# RFWBBoard.net
KiCad netlist of a schematic drawn in EAGLE
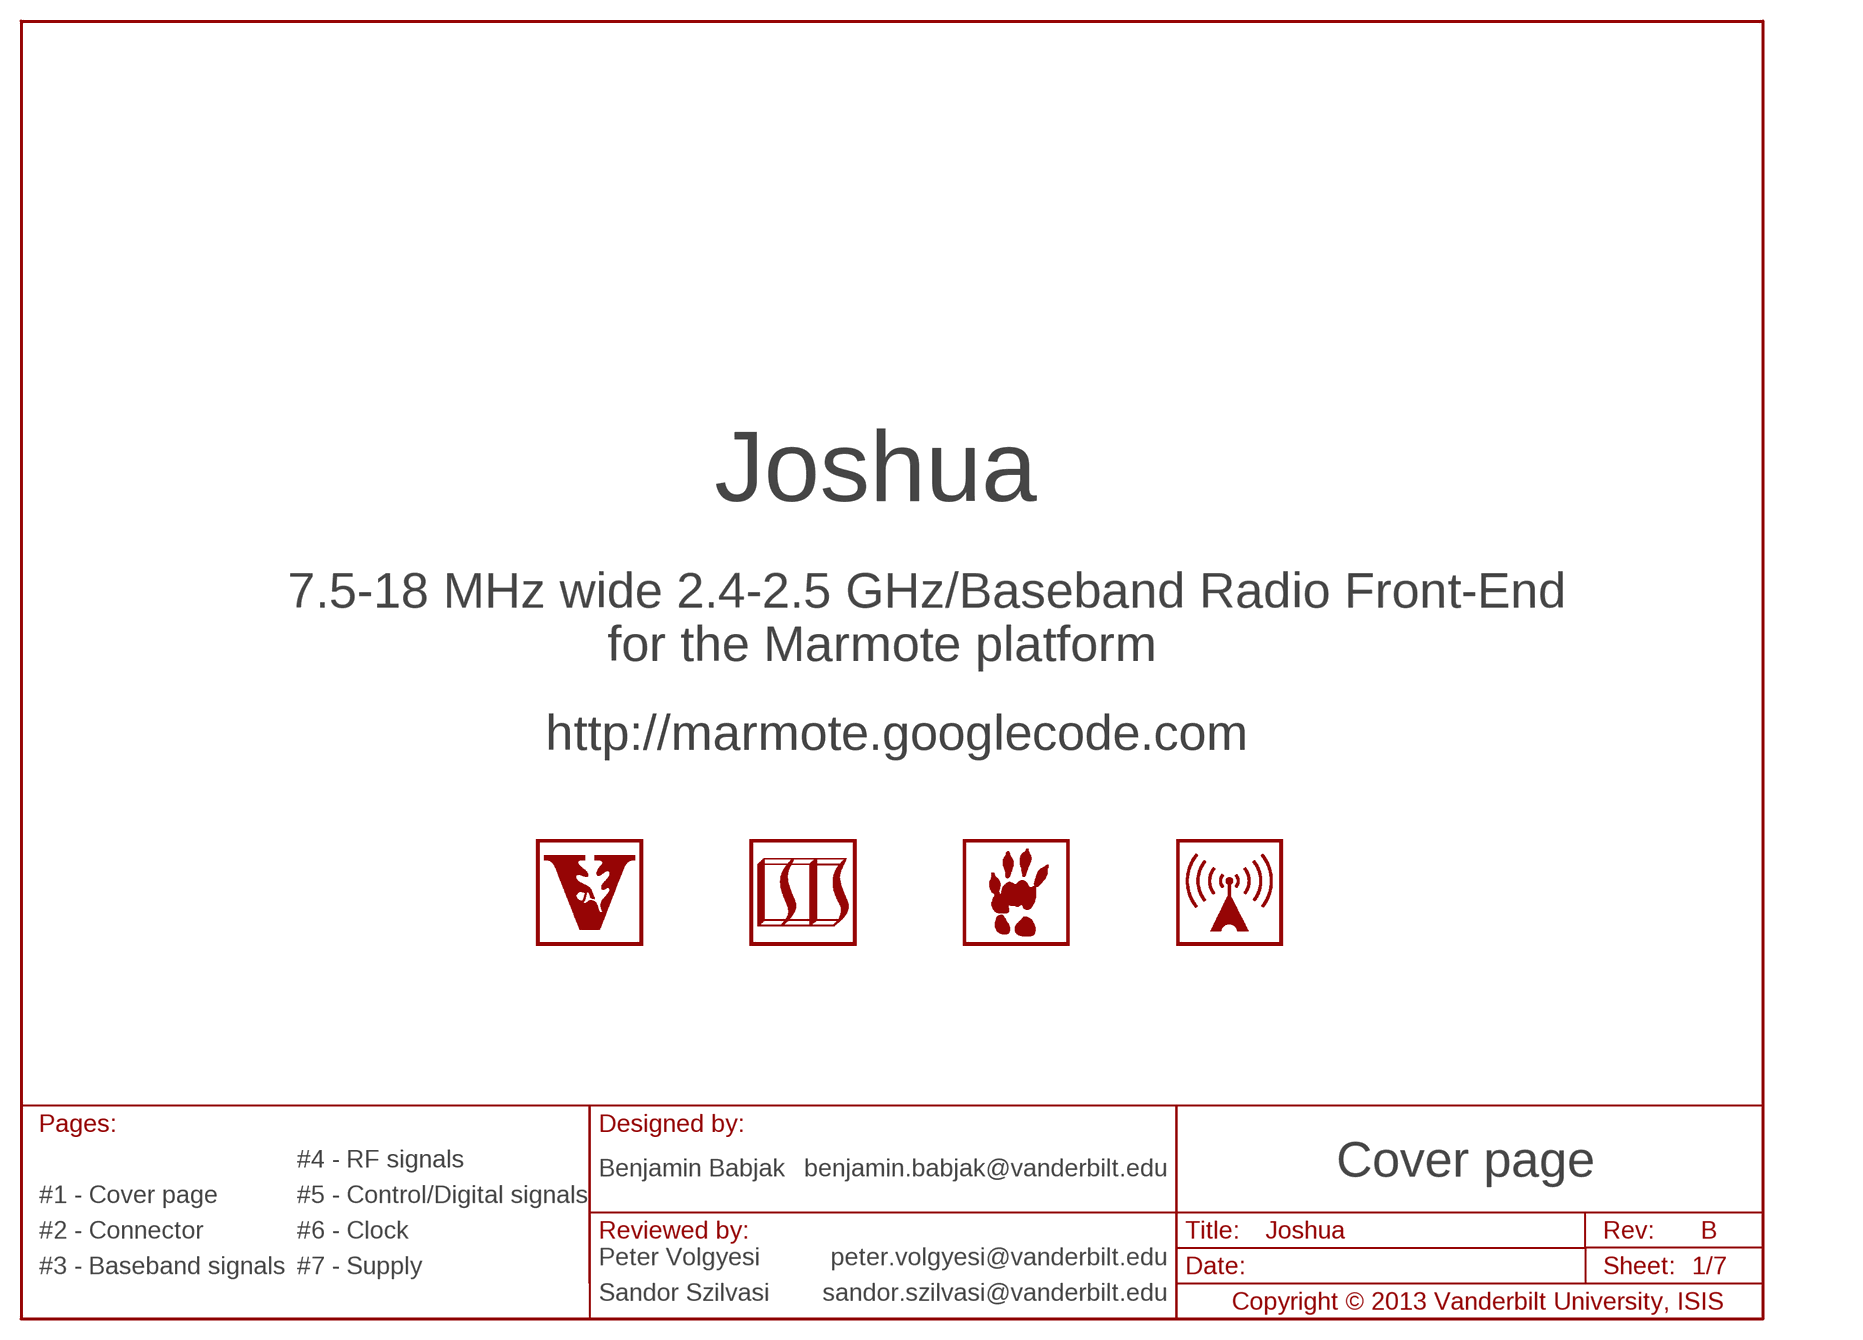
[diagram p0: schematic, sheet 1]
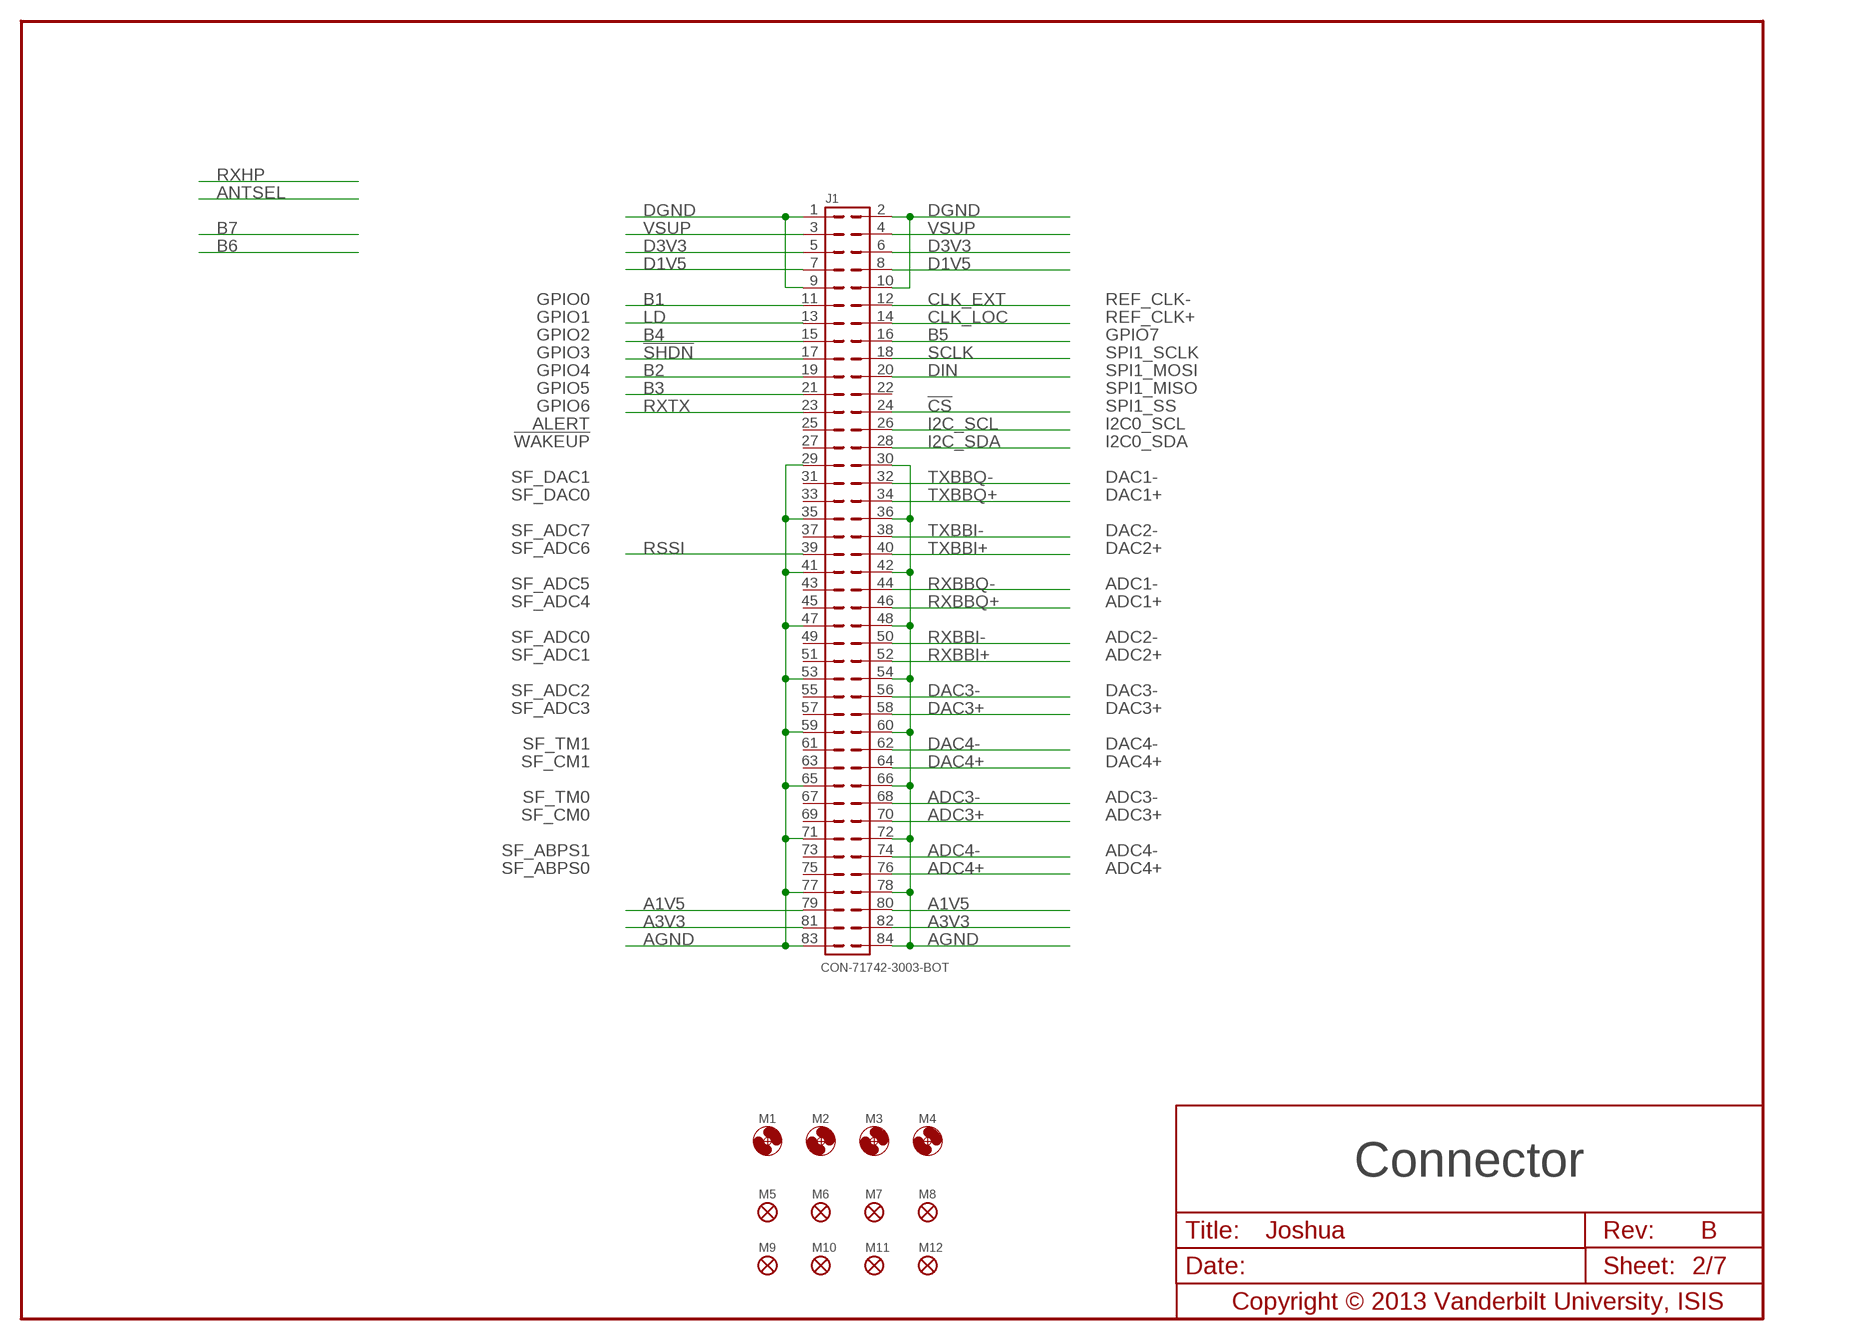
[diagram p1: schematic, sheet 2]
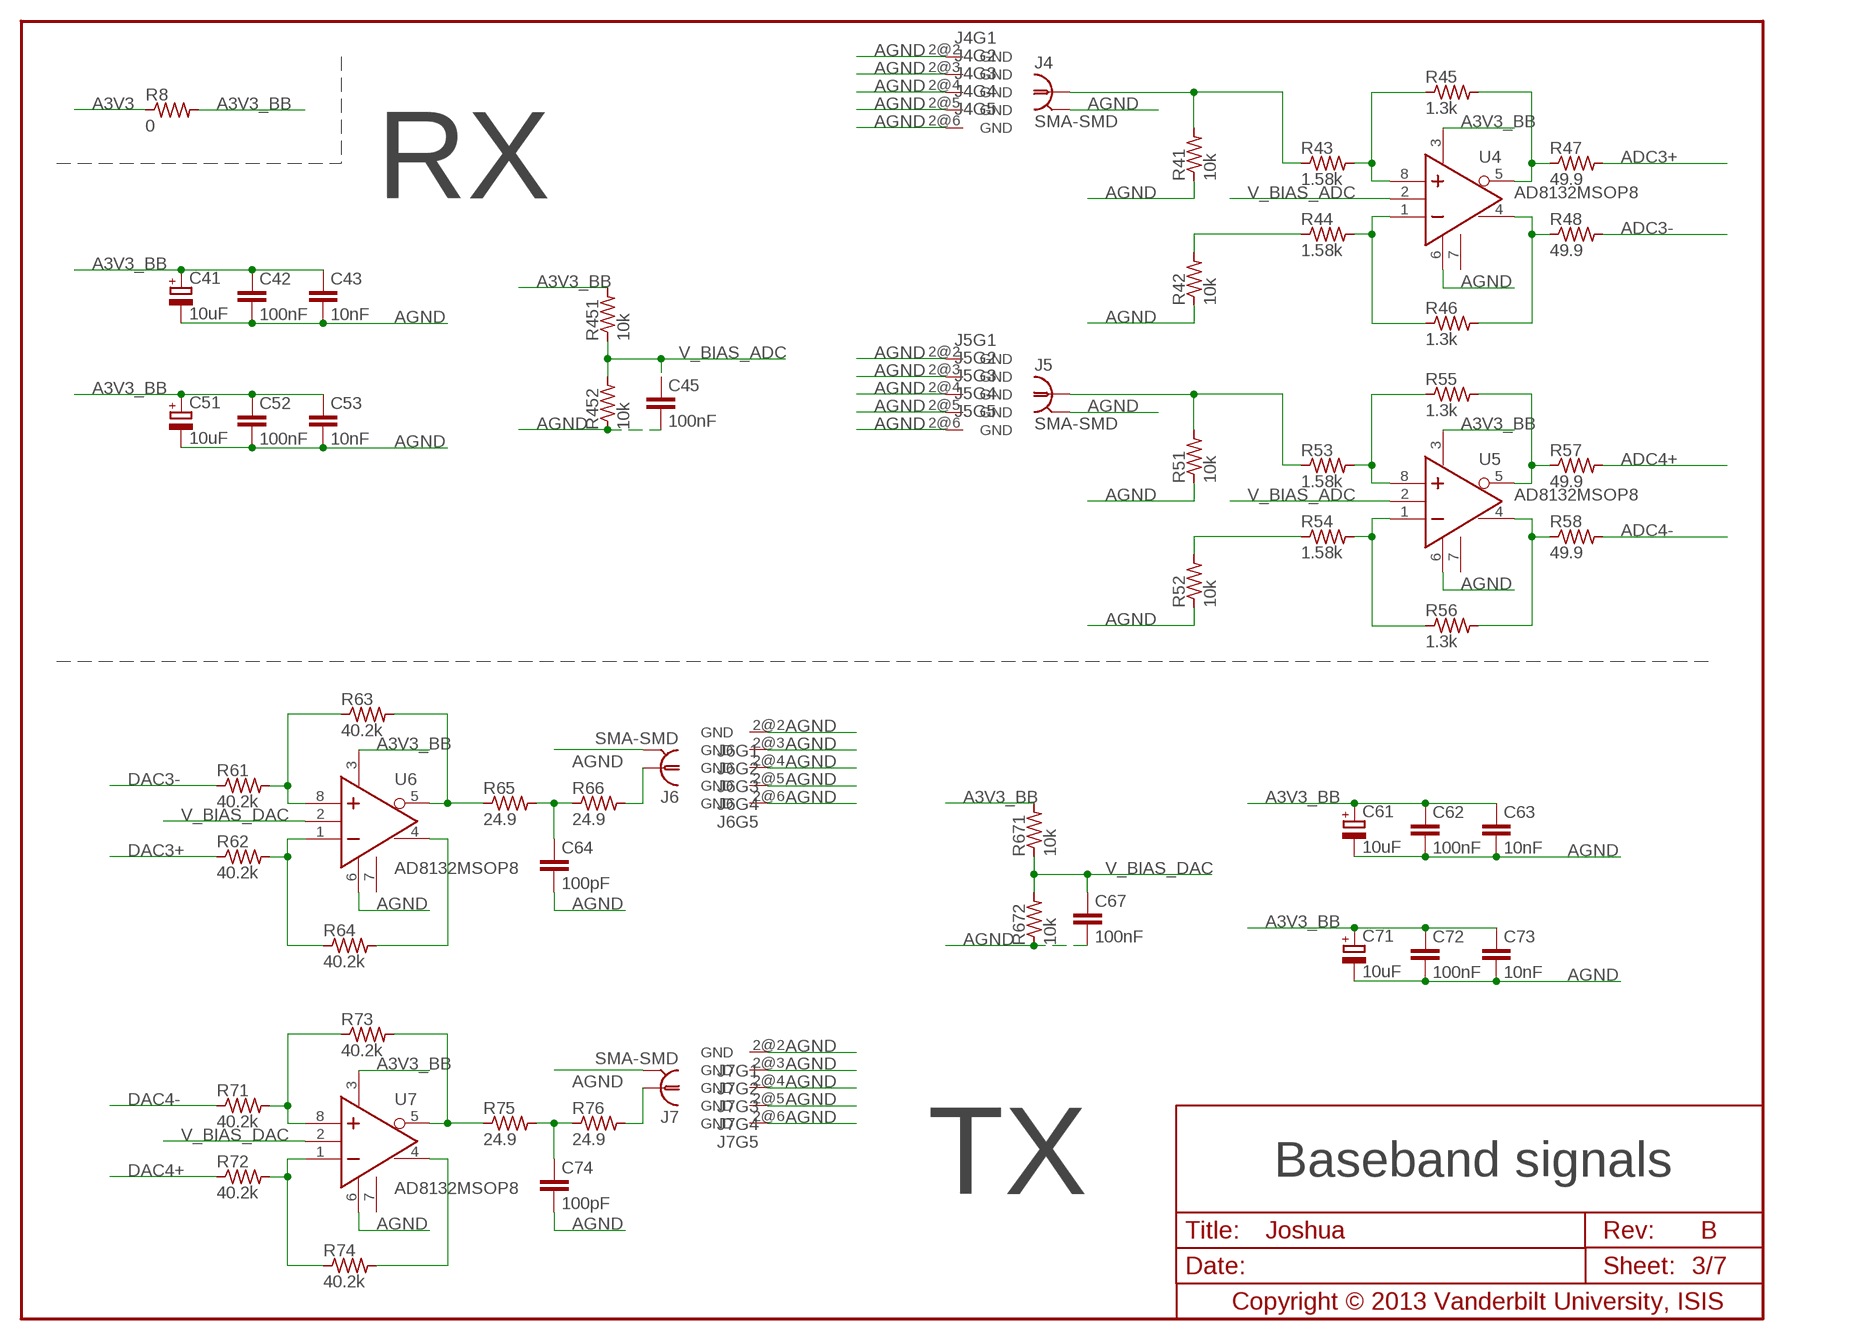
[diagram p2: schematic, sheet 3]
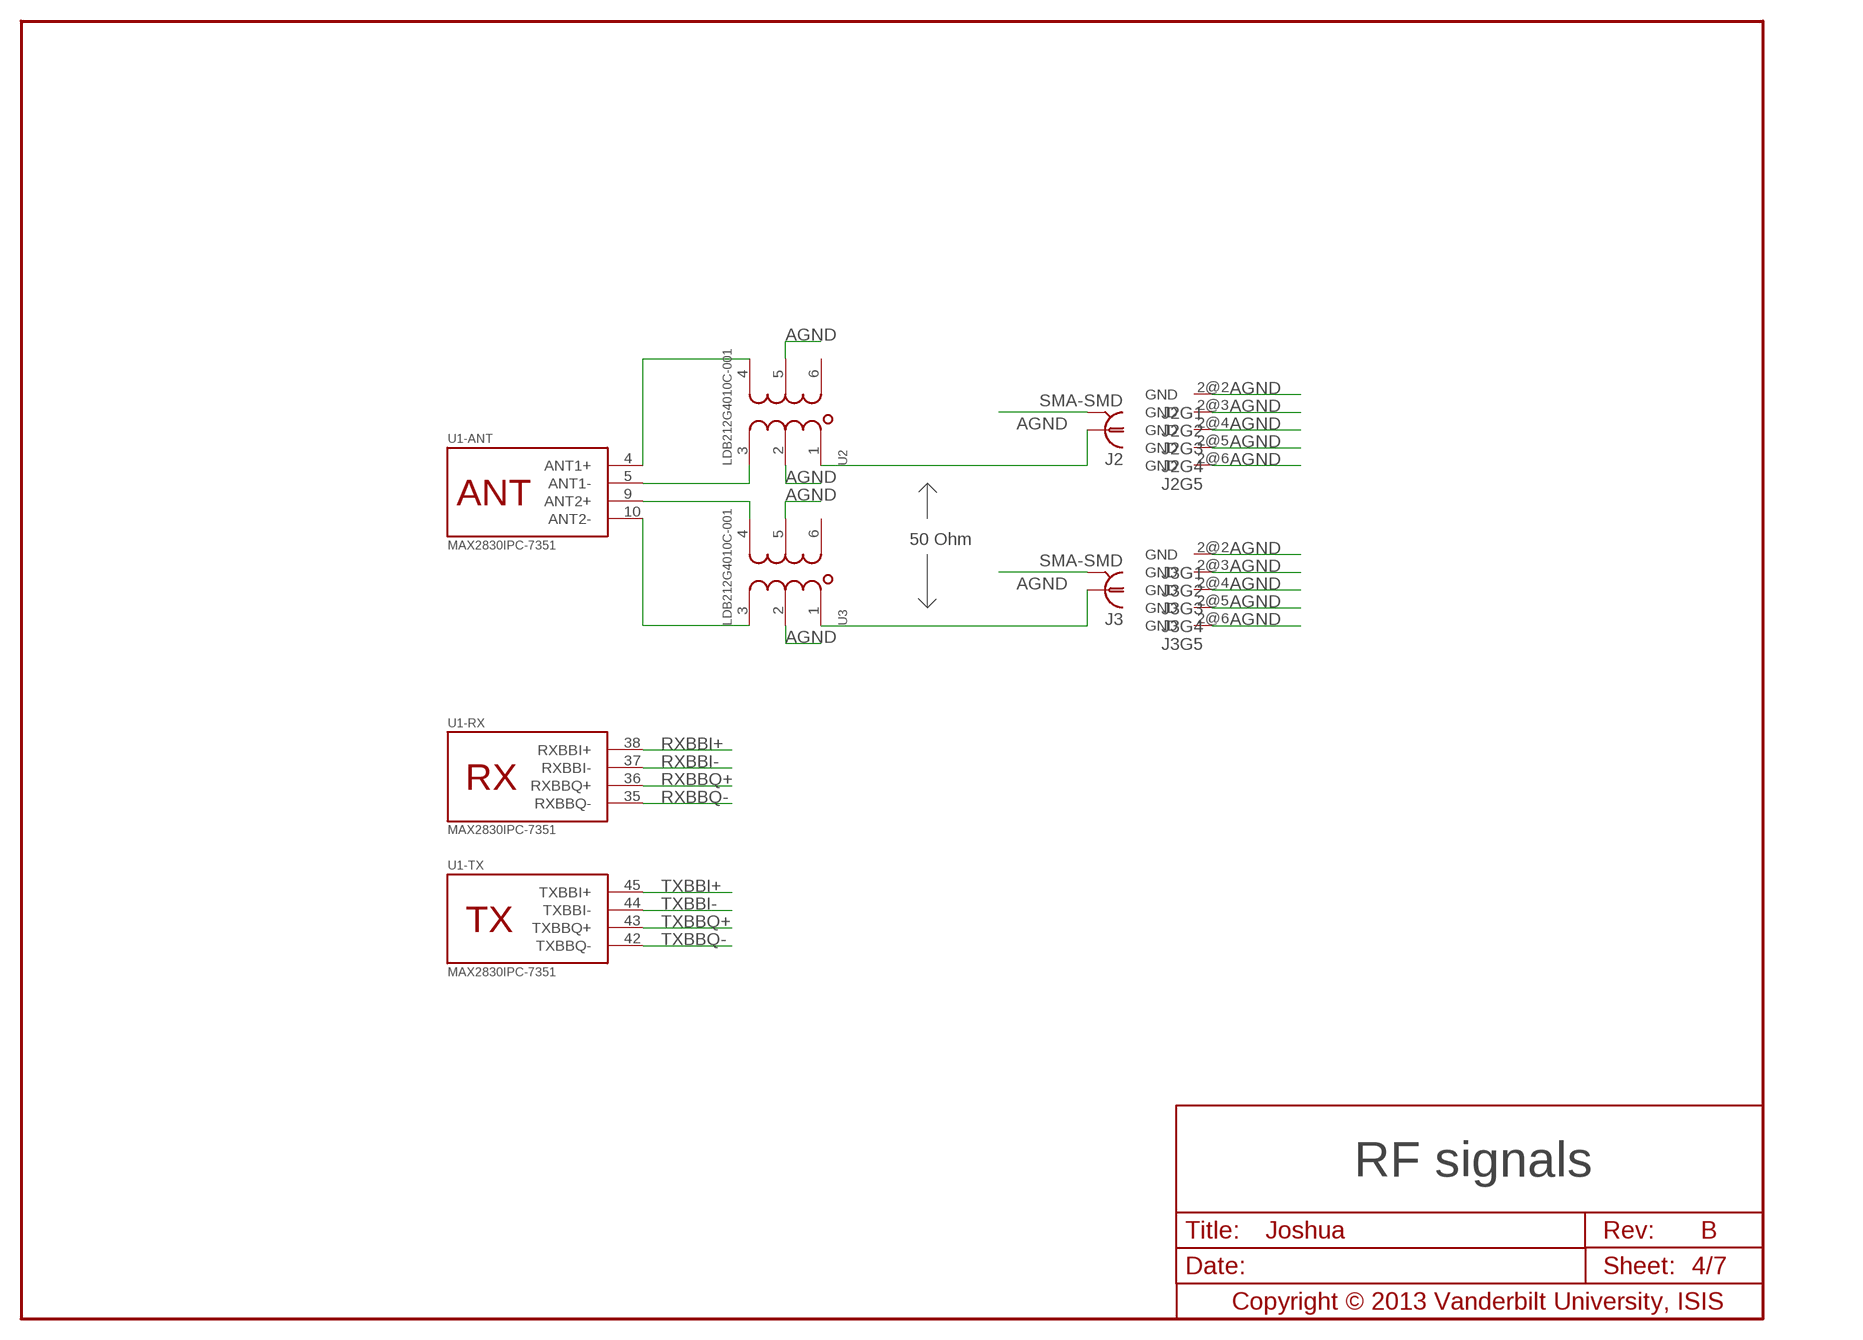
[diagram p3: schematic, sheet 4]
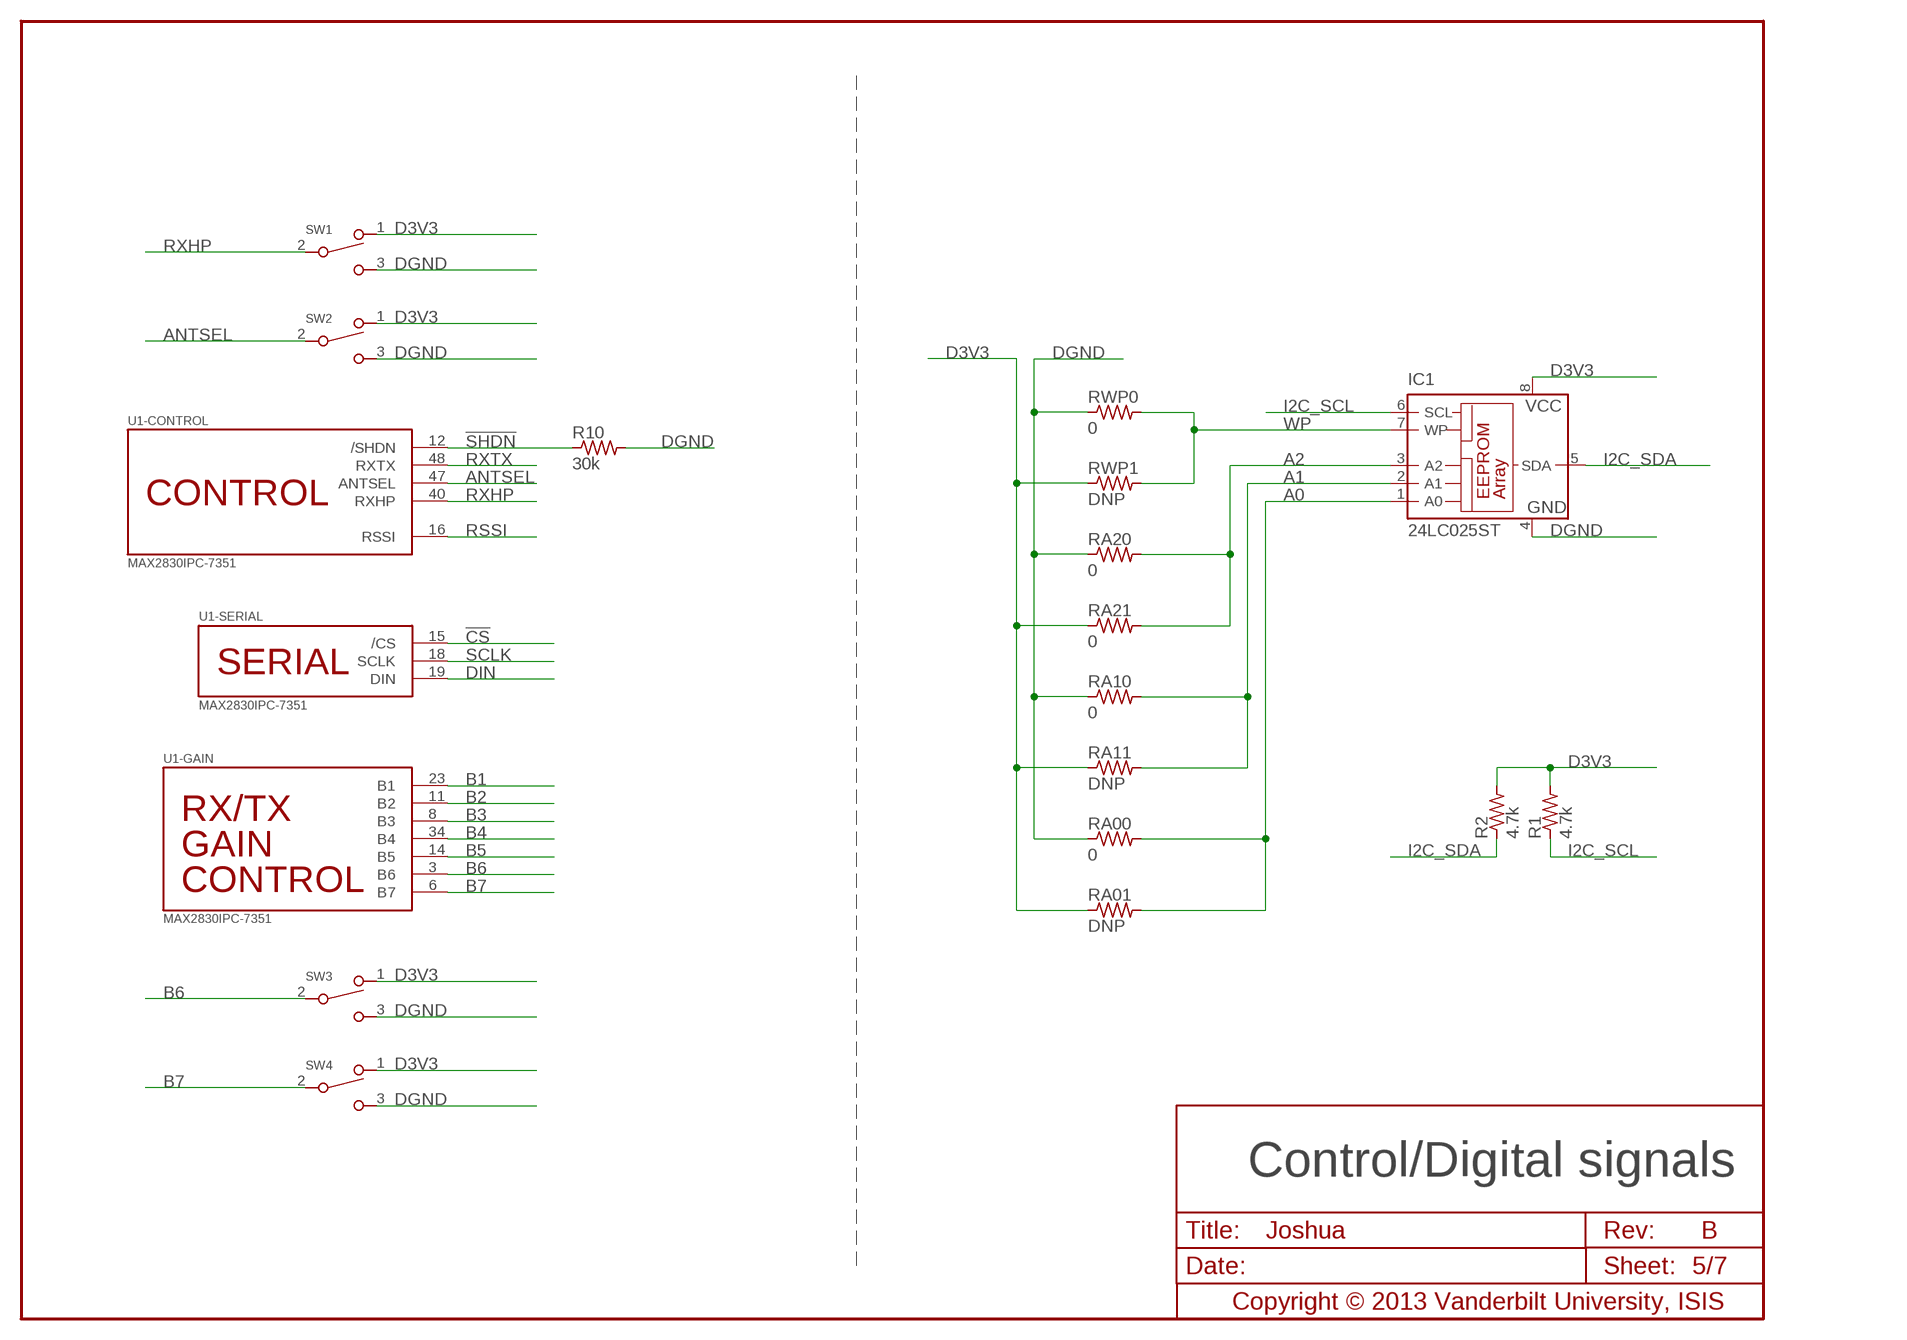
[diagram p4: schematic, sheet 5]
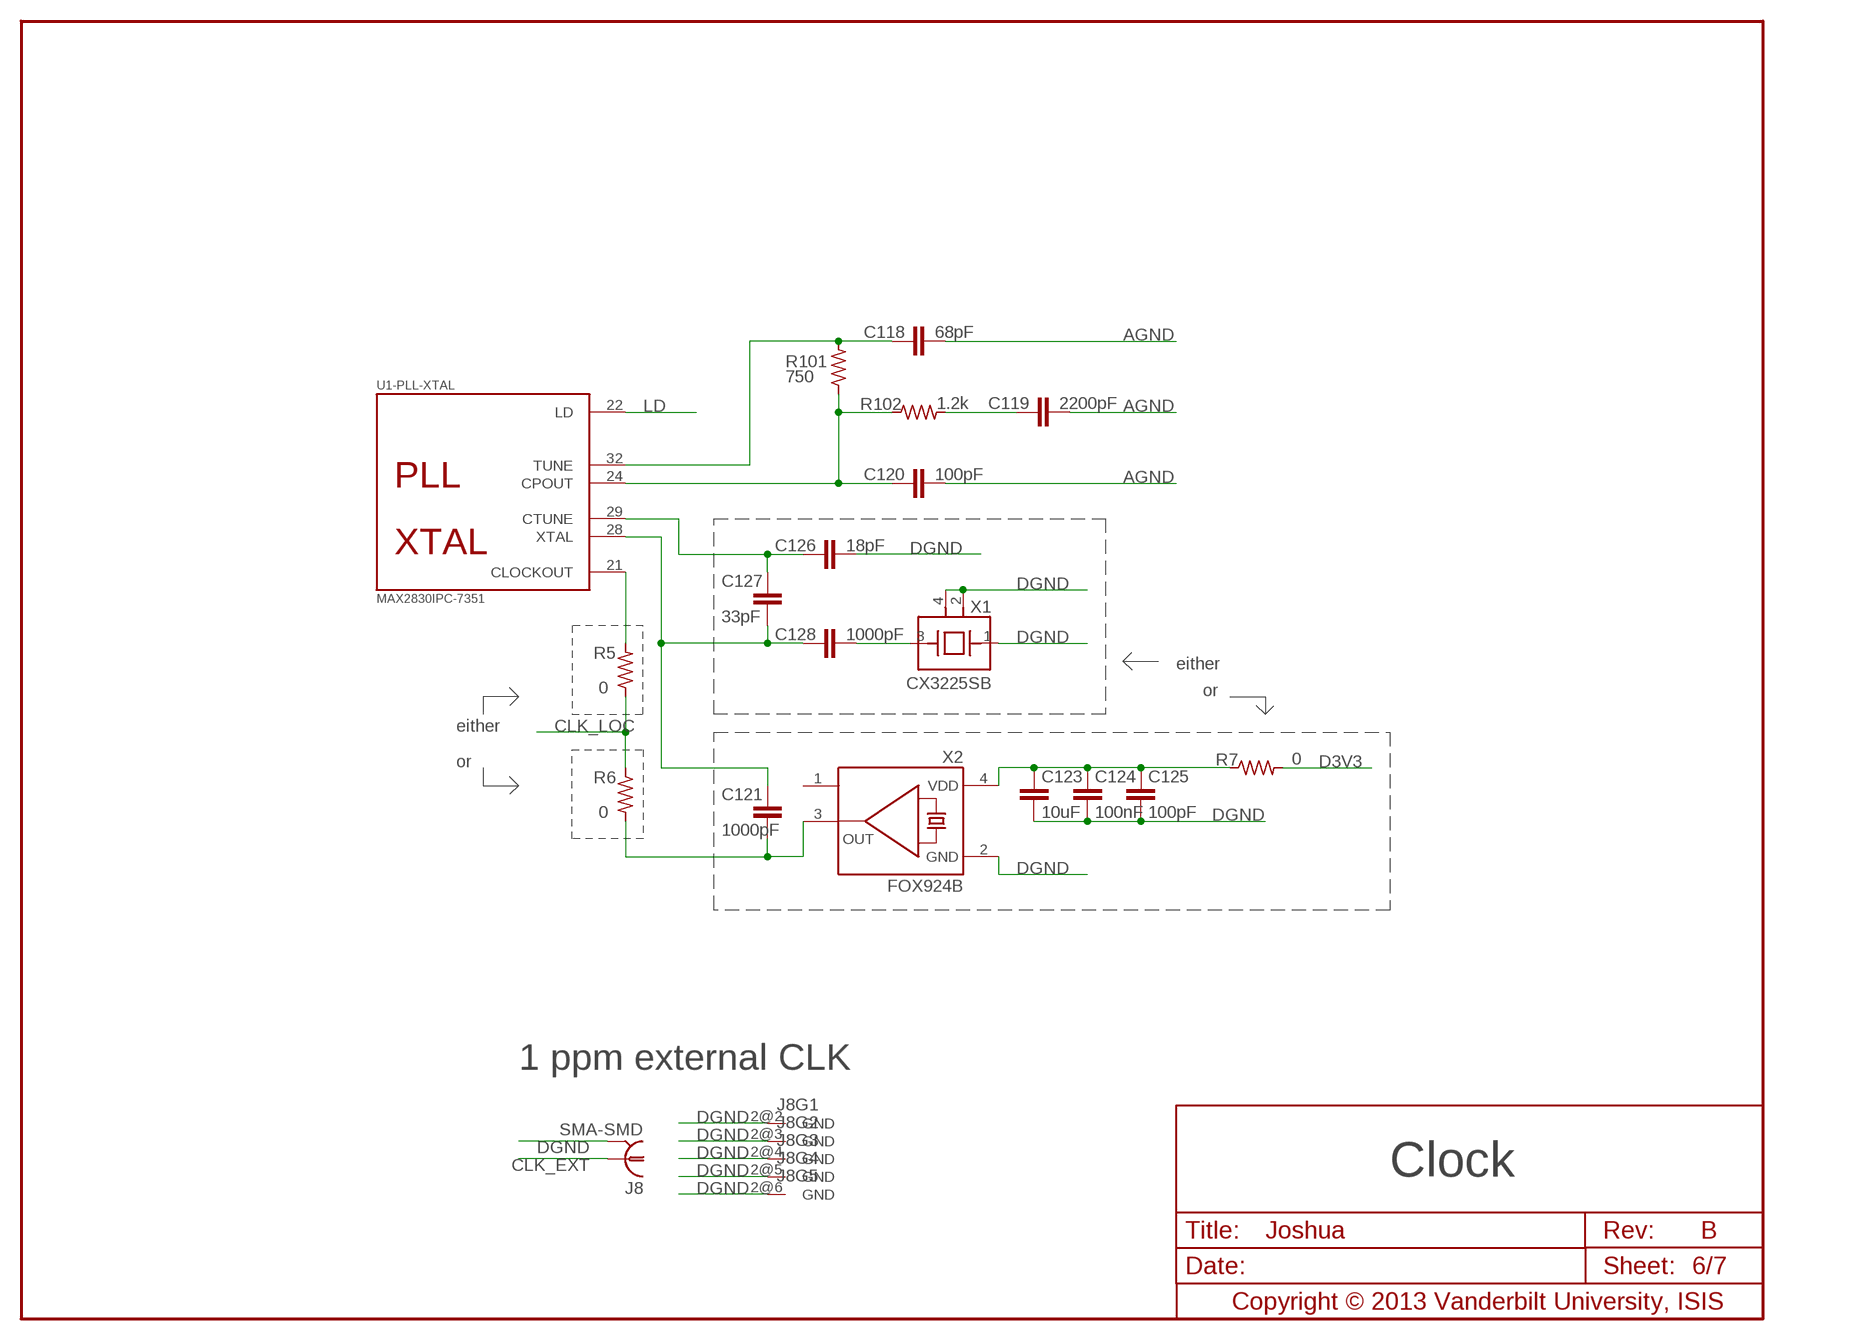
[diagram p5: schematic, sheet 6]
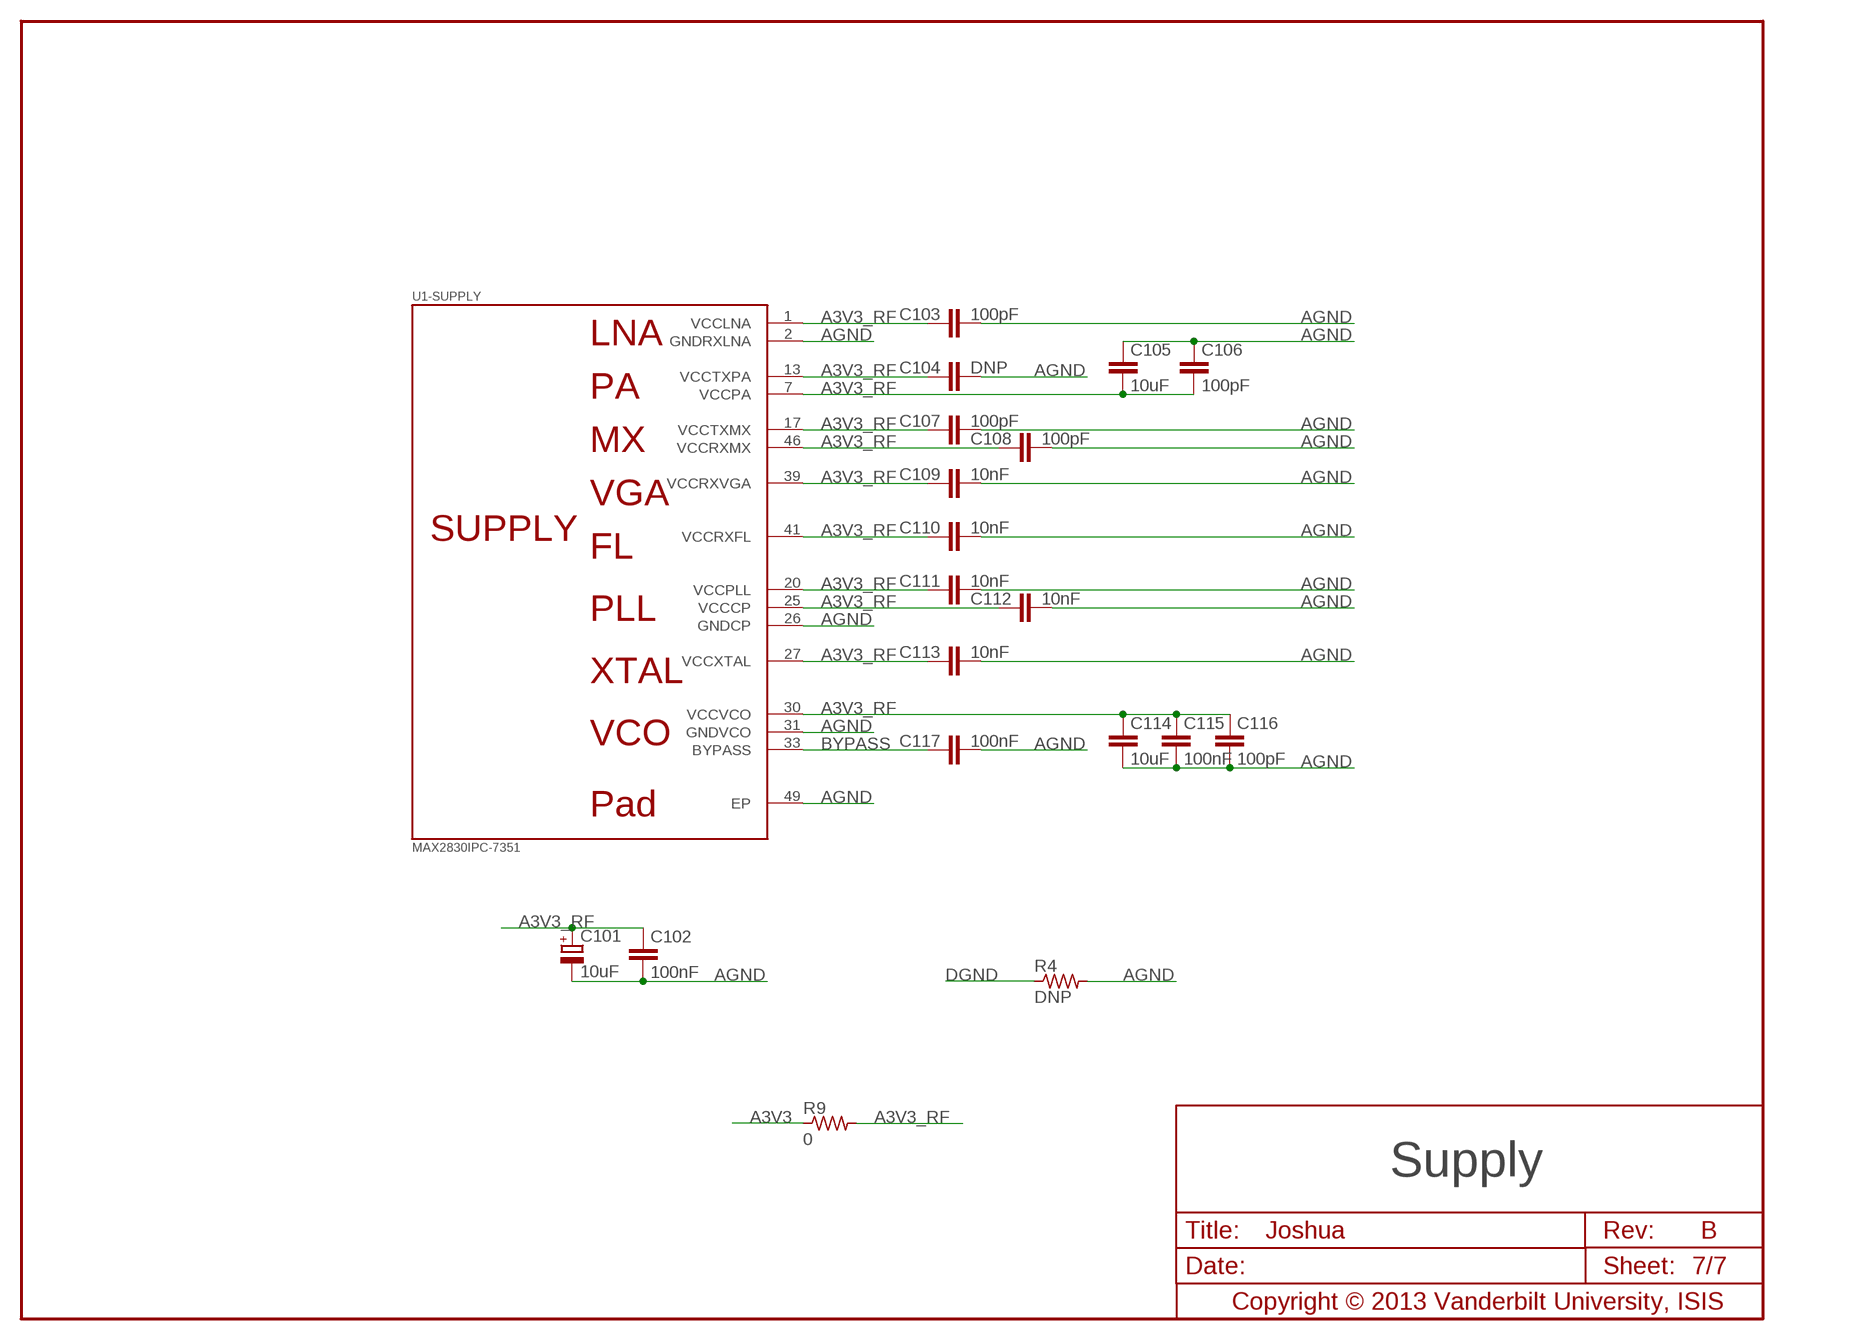
[diagram p6: schematic, sheet 7]

(export (version "E")
  (design (tool "Eeschema 10.0.6"))
  (components
    (comp (ref "IC1")
      (value "24LC025ST")
      (footprint "eagle-import:TSSOP8")
      (fields (field (name "MF") "MICROCHIP") (field (name "MPN") "24LC025-I/ST"))
      (libsource (lib "eagle-import") (part "24STLC025"))
    )
    (comp (ref "R1")
      (value "4.7k")
      (footprint "eagle-import:R0402")
      (libsource (lib "eagle-import") (part "R0402"))
    )
    (comp (ref "R2")
      (value "4.7k")
      (footprint "eagle-import:R0402")
      (libsource (lib "eagle-import") (part "R0402"))
    )
    (comp (ref "R10")
      (value "30k")
      (footprint "eagle-import:R0402")
      (libsource (lib "eagle-import") (part "R0402"))
    )
    (comp (ref "RA00")
      (value "0")
      (footprint "eagle-import:R0402")
      (libsource (lib "eagle-import") (part "R0402"))
    )
    (comp (ref "RA01")
      (value "DNP")
      (footprint "eagle-import:R0402")
      (libsource (lib "eagle-import") (part "R0402"))
    )
    (comp (ref "RA10")
      (value "0")
      (footprint "eagle-import:R0402")
      (libsource (lib "eagle-import") (part "R0402"))
    )
    (comp (ref "RA11")
      (value "DNP")
      (footprint "eagle-import:R0402")
      (libsource (lib "eagle-import") (part "R0402"))
    )
    (comp (ref "RA20")
      (value "0")
      (footprint "eagle-import:R0402")
      (libsource (lib "eagle-import") (part "R0402"))
    )
    (comp (ref "RA21")
      (value "0")
      (footprint "eagle-import:R0402")
      (libsource (lib "eagle-import") (part "R0402"))
    )
    (comp (ref "RWP0")
      (value "0")
      (footprint "eagle-import:R0402")
      (libsource (lib "eagle-import") (part "R0402"))
    )
    (comp (ref "RWP1")
      (value "DNP")
      (footprint "eagle-import:R0402")
      (libsource (lib "eagle-import") (part "R0402"))
    )
    (comp (ref "SW1")
      (value "SWITCH-CJS-1200TA")
      (footprint "eagle-import:SWITCH-DIP-CJS")
      (fields (field (name "MF") "CJS") (field (name "MPN") "CJS-1200TA"))
      (libsource (lib "eagle-import") (part "SWITCH-CJS-1200TA"))
    )
    (comp (ref "SW2")
      (value "SWITCH-CJS-1200TA")
      (footprint "eagle-import:SWITCH-DIP-CJS")
      (fields (field (name "MF") "CJS") (field (name "MPN") "CJS-1200TA"))
      (libsource (lib "eagle-import") (part "SWITCH-CJS-1200TA"))
    )
    (comp (ref "SW3")
      (value "SWITCH-CJS-1200TA")
      (footprint "eagle-import:SWITCH-DIP-CJS")
      (fields (field (name "MF") "CJS") (field (name "MPN") "CJS-1200TA"))
      (libsource (lib "eagle-import") (part "SWITCH-CJS-1200TA"))
    )
    (comp (ref "SW4")
      (value "SWITCH-CJS-1200TA")
      (footprint "eagle-import:SWITCH-DIP-CJS")
      (fields (field (name "MF") "CJS") (field (name "MPN") "CJS-1200TA"))
      (libsource (lib "eagle-import") (part "SWITCH-CJS-1200TA"))
    )
    (comp (ref "U1")
      (value "MAX2830IPC-7351")
      (footprint "eagle-import:TQFN-48")
      (libsource (lib "eagle-import") (part "MAX2830IPC-7351"))
    )
    (comp (ref "C118")
      (value "68pF")
      (footprint "eagle-import:C0402")
      (libsource (lib "eagle-import") (part "C0402"))
    )
    (comp (ref "C119")
      (value "2200pF")
      (footprint "eagle-import:C0402")
      (libsource (lib "eagle-import") (part "C0402"))
    )
    (comp (ref "C120")
      (value "100pF")
      (footprint "eagle-import:C0402")
      (libsource (lib "eagle-import") (part "C0402"))
    )
    (comp (ref "C121")
      (value "1000pF")
      (footprint "eagle-import:C0402")
      (libsource (lib "eagle-import") (part "C0402"))
    )
    (comp (ref "C123")
      (value "10uF")
      (footprint "eagle-import:C0805")
      (libsource (lib "eagle-import") (part "C0805"))
    )
    (comp (ref "C124")
      (value "100nF")
      (footprint "eagle-import:C0402")
      (libsource (lib "eagle-import") (part "C0402"))
    )
    (comp (ref "C125")
      (value "100pF")
      (footprint "eagle-import:C0402")
      (libsource (lib "eagle-import") (part "C0402"))
    )
    (comp (ref "C126")
      (value "18pF")
      (footprint "eagle-import:C0402")
      (libsource (lib "eagle-import") (part "C0402"))
    )
    (comp (ref "C127")
      (value "33pF")
      (footprint "eagle-import:C0402")
      (libsource (lib "eagle-import") (part "C0402"))
    )
    (comp (ref "C128")
      (value "1000pF")
      (footprint "eagle-import:C0402")
      (libsource (lib "eagle-import") (part "C0402"))
    )
    (comp (ref "J8")
      (value "SMA-SMD")
      (footprint "eagle-import:SMA-SMD")
      (libsource (lib "eagle-import") (part "SMA-SMD"))
    )
    (comp (ref "R5")
      (value "0")
      (footprint "eagle-import:R0402")
      (libsource (lib "eagle-import") (part "R0402"))
    )
    (comp (ref "R6")
      (value "0")
      (footprint "eagle-import:R0402")
      (libsource (lib "eagle-import") (part "R0402"))
    )
    (comp (ref "R7")
      (value "0")
      (footprint "eagle-import:R1206")
      (libsource (lib "eagle-import") (part "R1206"))
    )
    (comp (ref "R101")
      (value "750")
      (footprint "eagle-import:R0402")
      (libsource (lib "eagle-import") (part "R0402"))
    )
    (comp (ref "R102")
      (value "1.2k")
      (footprint "eagle-import:R0402")
      (libsource (lib "eagle-import") (part "R0402"))
    )
    (comp (ref "X1")
      (value "CX3225SB")
      (footprint "eagle-import:CX3225SB")
      (libsource (lib "eagle-import") (part "CX3225SB"))
    )
    (comp (ref "X2")
      (value "FOX924B")
      (footprint "eagle-import:FOX924")
      (fields (field (name "MF") "Fox Electronics") (field (name "MPN") "FOX924B-20.000"))
      (libsource (lib "eagle-import") (part "FOX924B"))
    )
    (comp (ref "C101")
      (value "10uF")
      (footprint "eagle-import:CPOL2012")
      (libsource (lib "eagle-import") (part "CPOL2012"))
    )
    (comp (ref "C102")
      (value "100nF")
      (footprint "eagle-import:C0402")
      (libsource (lib "eagle-import") (part "C0402"))
    )
    (comp (ref "C103")
      (value "100pF")
      (footprint "eagle-import:C0402")
      (libsource (lib "eagle-import") (part "C0402"))
    )
    (comp (ref "C104")
      (value "DNP")
      (footprint "eagle-import:C0402")
      (libsource (lib "eagle-import") (part "C0402"))
    )
    (comp (ref "C105")
      (value "10uF")
      (footprint "eagle-import:C1206")
      (libsource (lib "eagle-import") (part "C1206"))
    )
    (comp (ref "C106")
      (value "100pF")
      (footprint "eagle-import:C0402")
      (libsource (lib "eagle-import") (part "C0402"))
    )
    (comp (ref "C107")
      (value "100pF")
      (footprint "eagle-import:C0402")
      (libsource (lib "eagle-import") (part "C0402"))
    )
    (comp (ref "C108")
      (value "100pF")
      (footprint "eagle-import:C0402")
      (libsource (lib "eagle-import") (part "C0402"))
    )
    (comp (ref "C109")
      (value "10nF")
      (footprint "eagle-import:C0402")
      (libsource (lib "eagle-import") (part "C0402"))
    )
    (comp (ref "C110")
      (value "10nF")
      (footprint "eagle-import:C0402")
      (libsource (lib "eagle-import") (part "C0402"))
    )
    (comp (ref "C111")
      (value "10nF")
      (footprint "eagle-import:C0402")
      (libsource (lib "eagle-import") (part "C0402"))
    )
    (comp (ref "C112")
      (value "10nF")
      (footprint "eagle-import:C0402")
      (libsource (lib "eagle-import") (part "C0402"))
    )
    (comp (ref "C113")
      (value "10nF")
      (footprint "eagle-import:C0402")
      (libsource (lib "eagle-import") (part "C0402"))
    )
    (comp (ref "C114")
      (value "10uF")
      (footprint "eagle-import:C0805")
      (libsource (lib "eagle-import") (part "C0805"))
    )
    (comp (ref "C115")
      (value "100nF")
      (footprint "eagle-import:C0402")
      (libsource (lib "eagle-import") (part "C0402"))
    )
    (comp (ref "C116")
      (value "100pF")
      (footprint "eagle-import:C0402")
      (libsource (lib "eagle-import") (part "C0402"))
    )
    (comp (ref "C117")
      (value "100nF")
      (footprint "eagle-import:C0402")
      (libsource (lib "eagle-import") (part "C0402"))
    )
    (comp (ref "R4")
      (value "DNP")
      (footprint "eagle-import:R1206")
      (libsource (lib "eagle-import") (part "R1206"))
    )
    (comp (ref "R9")
      (value "0")
      (footprint "eagle-import:R1206")
      (libsource (lib "eagle-import") (part "R1206"))
    )
    (comp (ref "C41")
      (value "10uF")
      (footprint "eagle-import:CPOL2012")
      (libsource (lib "eagle-import") (part "CPOL2012"))
    )
    (comp (ref "C42")
      (value "100nF")
      (footprint "eagle-import:C0402")
      (libsource (lib "eagle-import") (part "C0402"))
    )
    (comp (ref "C43")
      (value "10nF")
      (footprint "eagle-import:C0402")
      (libsource (lib "eagle-import") (part "C0402"))
    )
    (comp (ref "C45")
      (value "100nF")
      (footprint "eagle-import:C0402")
      (libsource (lib "eagle-import") (part "C0402"))
    )
    (comp (ref "C51")
      (value "10uF")
      (footprint "eagle-import:CPOL2012")
      (libsource (lib "eagle-import") (part "CPOL2012"))
    )
    (comp (ref "C52")
      (value "100nF")
      (footprint "eagle-import:C0402")
      (libsource (lib "eagle-import") (part "C0402"))
    )
    (comp (ref "C53")
      (value "10nF")
      (footprint "eagle-import:C0402")
      (libsource (lib "eagle-import") (part "C0402"))
    )
    (comp (ref "C61")
      (value "10uF")
      (footprint "eagle-import:CPOL2012")
      (libsource (lib "eagle-import") (part "CPOL2012"))
    )
    (comp (ref "C62")
      (value "100nF")
      (footprint "eagle-import:C0402")
      (libsource (lib "eagle-import") (part "C0402"))
    )
    (comp (ref "C63")
      (value "10nF")
      (footprint "eagle-import:C0402")
      (libsource (lib "eagle-import") (part "C0402"))
    )
    (comp (ref "C64")
      (value "100pF")
      (footprint "eagle-import:C0402")
      (libsource (lib "eagle-import") (part "C0402"))
    )
    (comp (ref "C67")
      (value "100nF")
      (footprint "eagle-import:C0402")
      (libsource (lib "eagle-import") (part "C0402"))
    )
    (comp (ref "C71")
      (value "10uF")
      (footprint "eagle-import:CPOL2012")
      (libsource (lib "eagle-import") (part "CPOL2012"))
    )
    (comp (ref "C72")
      (value "100nF")
      (footprint "eagle-import:C0402")
      (libsource (lib "eagle-import") (part "C0402"))
    )
    (comp (ref "C73")
      (value "10nF")
      (footprint "eagle-import:C0402")
      (libsource (lib "eagle-import") (part "C0402"))
    )
    (comp (ref "C74")
      (value "100pF")
      (footprint "eagle-import:C0402")
      (libsource (lib "eagle-import") (part "C0402"))
    )
    (comp (ref "J4")
      (value "SMA-SMD")
      (footprint "eagle-import:SMA-SMD")
      (libsource (lib "eagle-import") (part "SMA-SMD"))
    )
    (comp (ref "J5")
      (value "SMA-SMD")
      (footprint "eagle-import:SMA-SMD")
      (libsource (lib "eagle-import") (part "SMA-SMD"))
    )
    (comp (ref "J6")
      (value "SMA-SMD")
      (footprint "eagle-import:SMA-SMD")
      (libsource (lib "eagle-import") (part "SMA-SMD"))
    )
    (comp (ref "J7")
      (value "SMA-SMD")
      (footprint "eagle-import:SMA-SMD")
      (libsource (lib "eagle-import") (part "SMA-SMD"))
    )
    (comp (ref "R8")
      (value "0")
      (footprint "eagle-import:R1206")
      (libsource (lib "eagle-import") (part "R1206"))
    )
    (comp (ref "R41")
      (value "10k")
      (footprint "eagle-import:R0402")
      (libsource (lib "eagle-import") (part "R0402"))
    )
    (comp (ref "R42")
      (value "10k")
      (footprint "eagle-import:R0402")
      (libsource (lib "eagle-import") (part "R0402"))
    )
    (comp (ref "R43")
      (value "1.58k")
      (footprint "eagle-import:R0402")
      (libsource (lib "eagle-import") (part "R0402"))
    )
    (comp (ref "R44")
      (value "1.58k")
      (footprint "eagle-import:R0402")
      (libsource (lib "eagle-import") (part "R0402"))
    )
    (comp (ref "R45")
      (value "1.3k")
      (footprint "eagle-import:R0402")
      (libsource (lib "eagle-import") (part "R0402"))
    )
    (comp (ref "R46")
      (value "1.3k")
      (footprint "eagle-import:R0402")
      (libsource (lib "eagle-import") (part "R0402"))
    )
    (comp (ref "R47")
      (value "49.9")
      (footprint "eagle-import:R0402")
      (libsource (lib "eagle-import") (part "R0402"))
    )
    (comp (ref "R48")
      (value "49.9")
      (footprint "eagle-import:R0402")
      (libsource (lib "eagle-import") (part "R0402"))
    )
    (comp (ref "R51")
      (value "10k")
      (footprint "eagle-import:R0402")
      (libsource (lib "eagle-import") (part "R0402"))
    )
    (comp (ref "R52")
      (value "10k")
      (footprint "eagle-import:R0402")
      (libsource (lib "eagle-import") (part "R0402"))
    )
    (comp (ref "R53")
      (value "1.58k")
      (footprint "eagle-import:R0402")
      (libsource (lib "eagle-import") (part "R0402"))
    )
    (comp (ref "R54")
      (value "1.58k")
      (footprint "eagle-import:R0402")
      (libsource (lib "eagle-import") (part "R0402"))
    )
    (comp (ref "R55")
      (value "1.3k")
      (footprint "eagle-import:R0402")
      (libsource (lib "eagle-import") (part "R0402"))
    )
    (comp (ref "R56")
      (value "1.3k")
      (footprint "eagle-import:R0402")
      (libsource (lib "eagle-import") (part "R0402"))
    )
    (comp (ref "R57")
      (value "49.9")
      (footprint "eagle-import:R0402")
      (libsource (lib "eagle-import") (part "R0402"))
    )
    (comp (ref "R58")
      (value "49.9")
      (footprint "eagle-import:R0402")
      (libsource (lib "eagle-import") (part "R0402"))
    )
    (comp (ref "R61")
      (value "40.2k")
      (footprint "eagle-import:R0402")
      (libsource (lib "eagle-import") (part "R0402"))
    )
    (comp (ref "R62")
      (value "40.2k")
      (footprint "eagle-import:R0402")
      (libsource (lib "eagle-import") (part "R0402"))
    )
    (comp (ref "R63")
      (value "40.2k")
      (footprint "eagle-import:R0402")
      (libsource (lib "eagle-import") (part "R0402"))
    )
    (comp (ref "R64")
      (value "40.2k")
      (footprint "eagle-import:R0402")
      (libsource (lib "eagle-import") (part "R0402"))
    )
    (comp (ref "R65")
      (value "24.9")
      (footprint "eagle-import:R0402")
      (libsource (lib "eagle-import") (part "R0402"))
    )
    (comp (ref "R66")
      (value "24.9")
      (footprint "eagle-import:R0402")
      (libsource (lib "eagle-import") (part "R0402"))
    )
    (comp (ref "R71")
      (value "40.2k")
      (footprint "eagle-import:R0402")
      (libsource (lib "eagle-import") (part "R0402"))
    )
    (comp (ref "R72")
      (value "40.2k")
      (footprint "eagle-import:R0402")
      (libsource (lib "eagle-import") (part "R0402"))
    )
    (comp (ref "R73")
      (value "40.2k")
      (footprint "eagle-import:R0402")
      (libsource (lib "eagle-import") (part "R0402"))
    )
    (comp (ref "R74")
      (value "40.2k")
      (footprint "eagle-import:R0402")
      (libsource (lib "eagle-import") (part "R0402"))
    )
    (comp (ref "R75")
      (value "24.9")
      (footprint "eagle-import:R0402")
      (libsource (lib "eagle-import") (part "R0402"))
    )
    (comp (ref "R76")
      (value "24.9")
      (footprint "eagle-import:R0402")
      (libsource (lib "eagle-import") (part "R0402"))
    )
    (comp (ref "R451")
      (value "10k")
      (footprint "eagle-import:R0402")
      (libsource (lib "eagle-import") (part "R0402"))
    )
    (comp (ref "R452")
      (value "10k")
      (footprint "eagle-import:R0402")
      (libsource (lib "eagle-import") (part "R0402"))
    )
    (comp (ref "R671")
      (value "10k")
      (footprint "eagle-import:R0402")
      (libsource (lib "eagle-import") (part "R0402"))
    )
    (comp (ref "R672")
      (value "10k")
      (footprint "eagle-import:R0402")
      (libsource (lib "eagle-import") (part "R0402"))
    )
    (comp (ref "U4")
      (value "AD8132MSOP8")
      (footprint "eagle-import:MSOP8")
      (libsource (lib "eagle-import") (part "AD8132MSOP8"))
    )
    (comp (ref "U5")
      (value "AD8132MSOP8")
      (footprint "eagle-import:MSOP8")
      (libsource (lib "eagle-import") (part "AD8132MSOP8"))
    )
    (comp (ref "U6")
      (value "AD8132MSOP8")
      (footprint "eagle-import:MSOP8")
      (libsource (lib "eagle-import") (part "AD8132MSOP8"))
    )
    (comp (ref "U7")
      (value "AD8132MSOP8")
      (footprint "eagle-import:MSOP8")
      (libsource (lib "eagle-import") (part "AD8132MSOP8"))
    )
    (comp (ref "J1")
      (value "CON-71742-3003-BOT")
      (footprint "eagle-import:71742-3003-BOT")
      (libsource (lib "eagle-import") (part "CON-71742-3003-BOT"))
    )
    (comp (ref "M1")
      (value "MOUNT-HOLE3.3")
      (footprint "eagle-import:3,3")
      (libsource (lib "eagle-import") (part "MOUNT-HOLE3.3"))
    )
    (comp (ref "M2")
      (value "MOUNT-HOLE3.3")
      (footprint "eagle-import:3,3")
      (libsource (lib "eagle-import") (part "MOUNT-HOLE3.3"))
    )
    (comp (ref "M3")
      (value "MOUNT-HOLE3.3")
      (footprint "eagle-import:3,3")
      (libsource (lib "eagle-import") (part "MOUNT-HOLE3.3"))
    )
    (comp (ref "M4")
      (value "MOUNT-HOLE3.3")
      (footprint "eagle-import:3,3")
      (libsource (lib "eagle-import") (part "MOUNT-HOLE3.3"))
    )
    (comp (ref "M5")
      (value "FIDUCIAL1X2")
      (footprint "eagle-import:FIDUCIAL-1X2")
      (libsource (lib "eagle-import") (part "FIDUCIAL1X2"))
    )
    (comp (ref "M6")
      (value "FIDUCIAL1X2")
      (footprint "eagle-import:FIDUCIAL-1X2")
      (libsource (lib "eagle-import") (part "FIDUCIAL1X2"))
    )
    (comp (ref "M7")
      (value "FIDUCIAL1X2")
      (footprint "eagle-import:FIDUCIAL-1X2")
      (libsource (lib "eagle-import") (part "FIDUCIAL1X2"))
    )
    (comp (ref "M8")
      (value "FIDUCIAL1X2")
      (footprint "eagle-import:FIDUCIAL-1X2")
      (libsource (lib "eagle-import") (part "FIDUCIAL1X2"))
    )
    (comp (ref "M9")
      (value "FIDUCIAL1X2")
      (footprint "eagle-import:FIDUCIAL-1X2")
      (libsource (lib "eagle-import") (part "FIDUCIAL1X2"))
    )
    (comp (ref "M10")
      (value "FIDUCIAL1X2")
      (footprint "eagle-import:FIDUCIAL-1X2")
      (libsource (lib "eagle-import") (part "FIDUCIAL1X2"))
    )
    (comp (ref "M11")
      (value "FIDUCIAL1X2")
      (footprint "eagle-import:FIDUCIAL-1X2")
      (libsource (lib "eagle-import") (part "FIDUCIAL1X2"))
    )
    (comp (ref "M12")
      (value "FIDUCIAL1X2")
      (footprint "eagle-import:FIDUCIAL-1X2")
      (libsource (lib "eagle-import") (part "FIDUCIAL1X2"))
    )
    (comp (ref "J2")
      (value "SMA-SMD")
      (footprint "eagle-import:SMA-SMD")
      (libsource (lib "eagle-import") (part "SMA-SMD"))
    )
    (comp (ref "J3")
      (value "SMA-SMD")
      (footprint "eagle-import:SMA-SMD")
      (libsource (lib "eagle-import") (part "SMA-SMD"))
    )
    (comp (ref "U2")
      (value "LDB212G4010C-001")
      (footprint "eagle-import:LDB21-FOOTPRINT")
      (libsource (lib "eagle-import") (part "LDB212G4010C-001"))
    )
    (comp (ref "U3")
      (value "LDB212G4010C-001")
      (footprint "eagle-import:LDB21-FOOTPRINT")
      (libsource (lib "eagle-import") (part "LDB212G4010C-001"))
    )
    (comp (ref "LOGO4")
      (value "LOGO-ISIS-600MIL-10MM-SS")
      (footprint "eagle-import:LOGO-ISIS-10MM-SILKSCREEN")
      (libsource (lib "eagle-import") (part "LOGO-ISIS-600MIL-10MM-SS"))
    )
    (comp (ref "LOGO5")
      (value "LOGO-VANDERBILT-600MIL-10MM-SS")
      (footprint "eagle-import:LOGO-VANDERBILT-10MM-SILKSCREEN")
      (libsource (lib "eagle-import") (part "LOGO-VANDERBILT-600MIL-10MM-SS"))
    )
    (comp (ref "LOGO6")
      (value "LOGO-MARMOTE-600MIL-10MM-SS")
      (footprint "eagle-import:LOGO-MARMOTE-10MM-SILKSCREEN")
      (libsource (lib "eagle-import") (part "LOGO-MARMOTE-600MIL-10MM-SS"))
    )
    (comp (ref "LOGO7")
      (value "LOGO-RADIO-3-600MIL-10MM-SS")
      (footprint "eagle-import:LOGO-RADIO-FILLED-10MM-SILKSCREEN")
      (libsource (lib "eagle-import") (part "LOGO-RADIO-3-600MIL-10MM-SS"))
    )
  )
  (nets
    (net (code "1") (name "A0") (class "Default")
      (node (ref "IC1") (pin "1") (pinfunction "A0_1") (pintype "input"))
      (node (ref "RA00") (pin "2") (pinfunction "2_2") (pintype "passive"))
      (node (ref "RA01") (pin "2") (pinfunction "2_2") (pintype "passive"))
    )
    (net (code "2") (name "A1") (class "Default")
      (node (ref "IC1") (pin "2") (pinfunction "A1_2") (pintype "input"))
      (node (ref "RA10") (pin "2") (pinfunction "2_2") (pintype "passive"))
      (node (ref "RA11") (pin "2") (pinfunction "2_2") (pintype "passive"))
    )
    (net (code "3") (name "A1V5") (class "Default")
      (node (ref "J1") (pin "79") (pinfunction "79_79") (pintype "passive"))
      (node (ref "J1") (pin "80") (pinfunction "80_80") (pintype "passive"))
    )
    (net (code "4") (name "A2") (class "Default")
      (node (ref "IC1") (pin "3") (pinfunction "A2_3") (pintype "input"))
      (node (ref "RA20") (pin "2") (pinfunction "2_2") (pintype "passive"))
      (node (ref "RA21") (pin "2") (pinfunction "2_2") (pintype "passive"))
    )
    (net (code "5") (name "A3V3") (class "Default")
      (node (ref "J1") (pin "81") (pinfunction "81_81") (pintype "passive"))
      (node (ref "J1") (pin "82") (pinfunction "82_82") (pintype "passive"))
      (node (ref "R8") (pin "1") (pinfunction "1_1") (pintype "passive"))
      (node (ref "R9") (pin "1") (pinfunction "1_1") (pintype "passive"))
    )
    (net (code "6") (name "A3V3_BB") (class "Default")
      (node (ref "C41") (pin "+") (pinfunction "+_+") (pintype "passive"))
      (node (ref "C42") (pin "1") (pinfunction "1_1") (pintype "passive"))
      (node (ref "C43") (pin "1") (pinfunction "1_1") (pintype "passive"))
      (node (ref "C51") (pin "+") (pinfunction "+_+") (pintype "passive"))
      (node (ref "C52") (pin "1") (pinfunction "1_1") (pintype "passive"))
      (node (ref "C53") (pin "1") (pinfunction "1_1") (pintype "passive"))
      (node (ref "C61") (pin "+") (pinfunction "+_+") (pintype "passive"))
      (node (ref "C62") (pin "1") (pinfunction "1_1") (pintype "passive"))
      (node (ref "C63") (pin "1") (pinfunction "1_1") (pintype "passive"))
      (node (ref "C71") (pin "+") (pinfunction "+_+") (pintype "passive"))
      (node (ref "C72") (pin "1") (pinfunction "1_1") (pintype "passive"))
      (node (ref "C73") (pin "1") (pinfunction "1_1") (pintype "passive"))
      (node (ref "R451") (pin "2") (pinfunction "2_2") (pintype "passive"))
      (node (ref "R671") (pin "2") (pinfunction "2_2") (pintype "passive"))
      (node (ref "R8") (pin "2") (pinfunction "2_2") (pintype "passive"))
      (node (ref "U4") (pin "3") (pinfunction "V_S+_3") (pintype "power_in"))
      (node (ref "U5") (pin "3") (pinfunction "V_S+_3") (pintype "power_in"))
      (node (ref "U6") (pin "3") (pinfunction "V_S+_3") (pintype "power_in"))
      (node (ref "U7") (pin "3") (pinfunction "V_S+_3") (pintype "power_in"))
    )
    (net (code "7") (name "A3V3_RF") (class "Default")
      (node (ref "C101") (pin "+") (pinfunction "+_+") (pintype "passive"))
      (node (ref "C102") (pin "1") (pinfunction "1_1") (pintype "passive"))
      (node (ref "C103") (pin "1") (pinfunction "1_1") (pintype "passive"))
      (node (ref "C104") (pin "1") (pinfunction "1_1") (pintype "passive"))
      (node (ref "C105") (pin "2") (pinfunction "2_2") (pintype "passive"))
      (node (ref "C106") (pin "2") (pinfunction "2_2") (pintype "passive"))
      (node (ref "C107") (pin "1") (pinfunction "1_1") (pintype "passive"))
      (node (ref "C108") (pin "1") (pinfunction "1_1") (pintype "passive"))
      (node (ref "C109") (pin "1") (pinfunction "1_1") (pintype "passive"))
      (node (ref "C110") (pin "1") (pinfunction "1_1") (pintype "passive"))
      (node (ref "C111") (pin "1") (pinfunction "1_1") (pintype "passive"))
      (node (ref "C112") (pin "1") (pinfunction "1_1") (pintype "passive"))
      (node (ref "C113") (pin "1") (pinfunction "1_1") (pintype "passive"))
      (node (ref "C114") (pin "1") (pinfunction "1_1") (pintype "passive"))
      (node (ref "C115") (pin "1") (pinfunction "1_1") (pintype "passive"))
      (node (ref "C116") (pin "1") (pinfunction "1_1") (pintype "passive"))
      (node (ref "R9") (pin "2") (pinfunction "2_2") (pintype "passive"))
      (node (ref "U1") (pin "1") (pinfunction "VCCLNA_1") (pintype "power_in"))
      (node (ref "U1") (pin "13") (pinfunction "VCCTXPA_13") (pintype "power_in"))
      (node (ref "U1") (pin "17") (pinfunction "VCCTXMX_17") (pintype "power_in"))
      (node (ref "U1") (pin "20") (pinfunction "VCCPLL_20") (pintype "power_in"))
      (node (ref "U1") (pin "25") (pinfunction "VCCCP_25") (pintype "power_in"))
      (node (ref "U1") (pin "27") (pinfunction "VCCXTAL_27") (pintype "power_in"))
      (node (ref "U1") (pin "30") (pinfunction "VCCVCO_30") (pintype "power_in"))
      (node (ref "U1") (pin "39") (pinfunction "VCCRXVGA_39") (pintype "power_in"))
      (node (ref "U1") (pin "41") (pinfunction "VCCRXFL_41") (pintype "power_in"))
      (node (ref "U1") (pin "46") (pinfunction "VCCRXMX_46") (pintype "power_in"))
      (node (ref "U1") (pin "7") (pinfunction "VCCPA_7") (pintype "power_in"))
    )
    (net (code "8") (name "ADC3+") (class "Default")
      (node (ref "J1") (pin "70") (pinfunction "70_70") (pintype "passive"))
      (node (ref "R47") (pin "2") (pinfunction "2_2") (pintype "passive"))
    )
    (net (code "9") (name "ADC3-") (class "Default")
      (node (ref "J1") (pin "68") (pinfunction "68_68") (pintype "passive"))
      (node (ref "R48") (pin "2") (pinfunction "2_2") (pintype "passive"))
    )
    (net (code "10") (name "ADC4+") (class "Default")
      (node (ref "J1") (pin "76") (pinfunction "76_76") (pintype "passive"))
      (node (ref "R57") (pin "2") (pinfunction "2_2") (pintype "passive"))
    )
    (net (code "11") (name "ADC4-") (class "Default")
      (node (ref "J1") (pin "74") (pinfunction "74_74") (pintype "passive"))
      (node (ref "R58") (pin "2") (pinfunction "2_2") (pintype "passive"))
    )
    (net (code "12") (name "AGND") (class "Default")
      (node (ref "C101") (pin "-") (pinfunction "-_-") (pintype "passive"))
      (node (ref "C102") (pin "2") (pinfunction "2_2") (pintype "passive"))
      (node (ref "C103") (pin "2") (pinfunction "2_2") (pintype "passive"))
      (node (ref "C104") (pin "2") (pinfunction "2_2") (pintype "passive"))
      (node (ref "C105") (pin "1") (pinfunction "1_1") (pintype "passive"))
      (node (ref "C106") (pin "1") (pinfunction "1_1") (pintype "passive"))
      (node (ref "C107") (pin "2") (pinfunction "2_2") (pintype "passive"))
      (node (ref "C108") (pin "2") (pinfunction "2_2") (pintype "passive"))
      (node (ref "C109") (pin "2") (pinfunction "2_2") (pintype "passive"))
      (node (ref "C110") (pin "2") (pinfunction "2_2") (pintype "passive"))
      (node (ref "C111") (pin "2") (pinfunction "2_2") (pintype "passive"))
      (node (ref "C112") (pin "2") (pinfunction "2_2") (pintype "passive"))
      (node (ref "C113") (pin "2") (pinfunction "2_2") (pintype "passive"))
      (node (ref "C114") (pin "2") (pinfunction "2_2") (pintype "passive"))
      (node (ref "C115") (pin "2") (pinfunction "2_2") (pintype "passive"))
      (node (ref "C116") (pin "2") (pinfunction "2_2") (pintype "passive"))
      (node (ref "C117") (pin "2") (pinfunction "2_2") (pintype "passive"))
      (node (ref "C118") (pin "2") (pinfunction "2_2") (pintype "passive"))
      (node (ref "C119") (pin "2") (pinfunction "2_2") (pintype "passive"))
      (node (ref "C120") (pin "2") (pinfunction "2_2") (pintype "passive"))
      (node (ref "C41") (pin "-") (pinfunction "-_-") (pintype "passive"))
      (node (ref "C42") (pin "2") (pinfunction "2_2") (pintype "passive"))
      (node (ref "C43") (pin "2") (pinfunction "2_2") (pintype "passive"))
      (node (ref "C45") (pin "2") (pinfunction "2_2") (pintype "passive"))
      (node (ref "C51") (pin "-") (pinfunction "-_-") (pintype "passive"))
      (node (ref "C52") (pin "2") (pinfunction "2_2") (pintype "passive"))
      (node (ref "C53") (pin "2") (pinfunction "2_2") (pintype "passive"))
      (node (ref "C61") (pin "-") (pinfunction "-_-") (pintype "passive"))
      (node (ref "C62") (pin "2") (pinfunction "2_2") (pintype "passive"))
      (node (ref "C63") (pin "2") (pinfunction "2_2") (pintype "passive"))
      (node (ref "C64") (pin "2") (pinfunction "2_2") (pintype "passive"))
      (node (ref "C67") (pin "2") (pinfunction "2_2") (pintype "passive"))
      (node (ref "C71") (pin "-") (pinfunction "-_-") (pintype "passive"))
      (node (ref "C72") (pin "2") (pinfunction "2_2") (pintype "passive"))
      (node (ref "C73") (pin "2") (pinfunction "2_2") (pintype "passive"))
      (node (ref "C74") (pin "2") (pinfunction "2_2") (pintype "passive"))
      (node (ref "J1") (pin "29") (pinfunction "29_29") (pintype "passive"))
      (node (ref "J1") (pin "30") (pinfunction "30_30") (pintype "passive"))
      (node (ref "J1") (pin "35") (pinfunction "35_35") (pintype "passive"))
      (node (ref "J1") (pin "36") (pinfunction "36_36") (pintype "passive"))
      (node (ref "J1") (pin "41") (pinfunction "41_41") (pintype "passive"))
      (node (ref "J1") (pin "42") (pinfunction "42_42") (pintype "passive"))
      (node (ref "J1") (pin "47") (pinfunction "47_47") (pintype "passive"))
      (node (ref "J1") (pin "48") (pinfunction "48_48") (pintype "passive"))
      (node (ref "J1") (pin "53") (pinfunction "53_53") (pintype "passive"))
      (node (ref "J1") (pin "54") (pinfunction "54_54") (pintype "passive"))
      (node (ref "J1") (pin "59") (pinfunction "59_59") (pintype "passive"))
      (node (ref "J1") (pin "60") (pinfunction "60_60") (pintype "passive"))
      (node (ref "J1") (pin "65") (pinfunction "65_65") (pintype "passive"))
      (node (ref "J1") (pin "66") (pinfunction "66_66") (pintype "passive"))
      (node (ref "J1") (pin "71") (pinfunction "71_71") (pintype "passive"))
      (node (ref "J1") (pin "72") (pinfunction "72_72") (pintype "passive"))
      (node (ref "J1") (pin "77") (pinfunction "77_77") (pintype "passive"))
      (node (ref "J1") (pin "78") (pinfunction "78_78") (pintype "passive"))
      (node (ref "J1") (pin "83") (pinfunction "83_83") (pintype "passive"))
      (node (ref "J1") (pin "84") (pinfunction "84_84") (pintype "passive"))
      (node (ref "J2") (pin "2@1") (pinfunction "GND_2@1") (pintype "power_in"))
      (node (ref "J2") (pin "2@2") (pinfunction "GND_2@2") (pintype "power_in"))
      (node (ref "J2") (pin "2@3") (pinfunction "GND_2@3") (pintype "power_in"))
      (node (ref "J2") (pin "2@4") (pinfunction "GND_2@4") (pintype "power_in"))
      (node (ref "J2") (pin "2@5") (pinfunction "GND_2@5") (pintype "power_in"))
      (node (ref "J2") (pin "2@6") (pinfunction "GND_2@6") (pintype "power_in"))
      (node (ref "J3") (pin "2@1") (pinfunction "GND_2@1") (pintype "power_in"))
      (node (ref "J3") (pin "2@2") (pinfunction "GND_2@2") (pintype "power_in"))
      (node (ref "J3") (pin "2@3") (pinfunction "GND_2@3") (pintype "power_in"))
      (node (ref "J3") (pin "2@4") (pinfunction "GND_2@4") (pintype "power_in"))
      (node (ref "J3") (pin "2@5") (pinfunction "GND_2@5") (pintype "power_in"))
      (node (ref "J3") (pin "2@6") (pinfunction "GND_2@6") (pintype "power_in"))
      (node (ref "J4") (pin "2@1") (pinfunction "GND_2@1") (pintype "power_in"))
      (node (ref "J4") (pin "2@2") (pinfunction "GND_2@2") (pintype "power_in"))
      (node (ref "J4") (pin "2@3") (pinfunction "GND_2@3") (pintype "power_in"))
      (node (ref "J4") (pin "2@4") (pinfunction "GND_2@4") (pintype "power_in"))
      (node (ref "J4") (pin "2@5") (pinfunction "GND_2@5") (pintype "power_in"))
      (node (ref "J4") (pin "2@6") (pinfunction "GND_2@6") (pintype "power_in"))
      (node (ref "J5") (pin "2@1") (pinfunction "GND_2@1") (pintype "power_in"))
      (node (ref "J5") (pin "2@2") (pinfunction "GND_2@2") (pintype "power_in"))
      (node (ref "J5") (pin "2@3") (pinfunction "GND_2@3") (pintype "power_in"))
      (node (ref "J5") (pin "2@4") (pinfunction "GND_2@4") (pintype "power_in"))
      (node (ref "J5") (pin "2@5") (pinfunction "GND_2@5") (pintype "power_in"))
      (node (ref "J5") (pin "2@6") (pinfunction "GND_2@6") (pintype "power_in"))
      (node (ref "J6") (pin "2@1") (pinfunction "GND_2@1") (pintype "power_in"))
      (node (ref "J6") (pin "2@2") (pinfunction "GND_2@2") (pintype "power_in"))
      (node (ref "J6") (pin "2@3") (pinfunction "GND_2@3") (pintype "power_in"))
      (node (ref "J6") (pin "2@4") (pinfunction "GND_2@4") (pintype "power_in"))
      (node (ref "J6") (pin "2@5") (pinfunction "GND_2@5") (pintype "power_in"))
      (node (ref "J6") (pin "2@6") (pinfunction "GND_2@6") (pintype "power_in"))
      (node (ref "J7") (pin "2@1") (pinfunction "GND_2@1") (pintype "power_in"))
      (node (ref "J7") (pin "2@2") (pinfunction "GND_2@2") (pintype "power_in"))
      (node (ref "J7") (pin "2@3") (pinfunction "GND_2@3") (pintype "power_in"))
      (node (ref "J7") (pin "2@4") (pinfunction "GND_2@4") (pintype "power_in"))
      (node (ref "J7") (pin "2@5") (pinfunction "GND_2@5") (pintype "power_in"))
      (node (ref "J7") (pin "2@6") (pinfunction "GND_2@6") (pintype "power_in"))
      (node (ref "R4") (pin "2") (pinfunction "2_2") (pintype "passive"))
      (node (ref "R41") (pin "1") (pinfunction "1_1") (pintype "passive"))
      (node (ref "R42") (pin "1") (pinfunction "1_1") (pintype "passive"))
      (node (ref "R452") (pin "1") (pinfunction "1_1") (pintype "passive"))
      (node (ref "R51") (pin "1") (pinfunction "1_1") (pintype "passive"))
      (node (ref "R52") (pin "1") (pinfunction "1_1") (pintype "passive"))
      (node (ref "R672") (pin "1") (pinfunction "1_1") (pintype "passive"))
      (node (ref "U1") (pin "2") (pinfunction "GNDRXLNA_2") (pintype "power_in"))
      (node (ref "U1") (pin "26") (pinfunction "GNDCP_26") (pintype "power_in"))
      (node (ref "U1") (pin "31") (pinfunction "GNDVCO_31") (pintype "power_in"))
      (node (ref "U1") (pin "49") (pinfunction "EP_49") (pintype "power_in"))
      (node (ref "U2") (pin "2") (pinfunction "2_2") (pintype "power_in"))
      (node (ref "U2") (pin "5") (pinfunction "5_5") (pintype "power_in"))
      (node (ref "U3") (pin "2") (pinfunction "2_2") (pintype "power_in"))
      (node (ref "U3") (pin "5") (pinfunction "5_5") (pintype "power_in"))
      (node (ref "U4") (pin "6") (pinfunction "V_S-_6") (pintype "power_in"))
      (node (ref "U5") (pin "6") (pinfunction "V_S-_6") (pintype "power_in"))
      (node (ref "U6") (pin "6") (pinfunction "V_S-_6") (pintype "power_in"))
      (node (ref "U7") (pin "6") (pinfunction "V_S-_6") (pintype "power_in"))
    )
    (net (code "13") (name "ANTSEL") (class "Default")
      (node (ref "SW2") (pin "2") (pinfunction "2_2") (pintype "passive"))
      (node (ref "U1") (pin "47") (pinfunction "ANTSEL_47") (pintype "input"))
    )
    (net (code "14") (name "B1") (class "Default")
      (node (ref "J1") (pin "11") (pinfunction "11_11") (pintype "passive"))
      (node (ref "U1") (pin "23") (pinfunction "B1_23") (pintype "input"))
    )
    (net (code "15") (name "B2") (class "Default")
      (node (ref "J1") (pin "19") (pinfunction "19_19") (pintype "passive"))
      (node (ref "U1") (pin "11") (pinfunction "B2_11") (pintype "input"))
    )
    (net (code "16") (name "B3") (class "Default")
      (node (ref "J1") (pin "21") (pinfunction "21_21") (pintype "passive"))
      (node (ref "U1") (pin "8") (pinfunction "B3_8") (pintype "input"))
    )
    (net (code "17") (name "B4") (class "Default")
      (node (ref "J1") (pin "15") (pinfunction "15_15") (pintype "passive"))
      (node (ref "U1") (pin "34") (pinfunction "B4_34") (pintype "input"))
    )
    (net (code "18") (name "B5") (class "Default")
      (node (ref "J1") (pin "16") (pinfunction "16_16") (pintype "passive"))
      (node (ref "U1") (pin "14") (pinfunction "B5_14") (pintype "input"))
    )
    (net (code "19") (name "B6") (class "Default")
      (node (ref "SW3") (pin "2") (pinfunction "2_2") (pintype "passive"))
      (node (ref "U1") (pin "3") (pinfunction "B6_3") (pintype "input"))
    )
    (net (code "20") (name "B7") (class "Default")
      (node (ref "SW4") (pin "2") (pinfunction "2_2") (pintype "passive"))
      (node (ref "U1") (pin "6") (pinfunction "B7_6") (pintype "input"))
    )
    (net (code "21") (name "BYPASS") (class "Default")
      (node (ref "C117") (pin "1") (pinfunction "1_1") (pintype "passive"))
      (node (ref "U1") (pin "33") (pinfunction "BYPASS_33") (pintype "power_in"))
    )
    (net (code "22") (name "CLK_EXT") (class "Default")
      (node (ref "J1") (pin "12") (pinfunction "12_12") (pintype "passive"))
      (node (ref "J8") (pin "1") (pinfunction "1_1") (pintype "passive"))
    )
    (net (code "23") (name "CLK_LOC") (class "Default")
      (node (ref "J1") (pin "14") (pinfunction "14_14") (pintype "passive"))
      (node (ref "R5") (pin "1") (pinfunction "1_1") (pintype "passive"))
      (node (ref "R6") (pin "1") (pinfunction "1_1") (pintype "passive"))
    )
    (net (code "24") (name "D1V5") (class "Default")
      (node (ref "J1") (pin "7") (pinfunction "7_7") (pintype "passive"))
      (node (ref "J1") (pin "8") (pinfunction "8_8") (pintype "passive"))
    )
    (net (code "25") (name "D3V3") (class "Default")
      (node (ref "IC1") (pin "8") (pinfunction "VCC_8") (pintype "power_in"))
      (node (ref "J1") (pin "5") (pinfunction "5_5") (pintype "passive"))
      (node (ref "J1") (pin "6") (pinfunction "6_6") (pintype "passive"))
      (node (ref "R1") (pin "2") (pinfunction "2_2") (pintype "passive"))
      (node (ref "R2") (pin "2") (pinfunction "2_2") (pintype "passive"))
      (node (ref "R7") (pin "2") (pinfunction "2_2") (pintype "passive"))
      (node (ref "RA01") (pin "1") (pinfunction "1_1") (pintype "passive"))
      (node (ref "RA11") (pin "1") (pinfunction "1_1") (pintype "passive"))
      (node (ref "RA21") (pin "1") (pinfunction "1_1") (pintype "passive"))
      (node (ref "RWP1") (pin "1") (pinfunction "1_1") (pintype "passive"))
      (node (ref "SW1") (pin "1") (pinfunction "1_1") (pintype "passive"))
      (node (ref "SW2") (pin "1") (pinfunction "1_1") (pintype "passive"))
      (node (ref "SW3") (pin "1") (pinfunction "1_1") (pintype "passive"))
      (node (ref "SW4") (pin "1") (pinfunction "1_1") (pintype "passive"))
    )
    (net (code "26") (name "DAC3+") (class "Default")
      (node (ref "J1") (pin "58") (pinfunction "58_58") (pintype "passive"))
      (node (ref "R62") (pin "1") (pinfunction "1_1") (pintype "passive"))
    )
    (net (code "27") (name "DAC3-") (class "Default")
      (node (ref "J1") (pin "56") (pinfunction "56_56") (pintype "passive"))
      (node (ref "R61") (pin "1") (pinfunction "1_1") (pintype "passive"))
    )
    (net (code "28") (name "DAC4+") (class "Default")
      (node (ref "J1") (pin "64") (pinfunction "64_64") (pintype "passive"))
      (node (ref "R72") (pin "1") (pinfunction "1_1") (pintype "passive"))
    )
    (net (code "29") (name "DAC4-") (class "Default")
      (node (ref "J1") (pin "62") (pinfunction "62_62") (pintype "passive"))
      (node (ref "R71") (pin "1") (pinfunction "1_1") (pintype "passive"))
    )
    (net (code "30") (name "DGND") (class "Default")
      (node (ref "C123") (pin "2") (pinfunction "2_2") (pintype "passive"))
      (node (ref "C124") (pin "2") (pinfunction "2_2") (pintype "passive"))
      (node (ref "C125") (pin "2") (pinfunction "2_2") (pintype "passive"))
      (node (ref "C126") (pin "1") (pinfunction "1_1") (pintype "passive"))
      (node (ref "IC1") (pin "4") (pinfunction "GND_4") (pintype "power_in"))
      (node (ref "J1") (pin "1") (pinfunction "1_1") (pintype "passive"))
      (node (ref "J1") (pin "10") (pinfunction "10_10") (pintype "passive"))
      (node (ref "J1") (pin "2") (pinfunction "2_2") (pintype "passive"))
      (node (ref "J1") (pin "9") (pinfunction "9_9") (pintype "passive"))
      (node (ref "J8") (pin "2@1") (pinfunction "GND_2@1") (pintype "power_in"))
      (node (ref "J8") (pin "2@2") (pinfunction "GND_2@2") (pintype "power_in"))
      (node (ref "J8") (pin "2@3") (pinfunction "GND_2@3") (pintype "power_in"))
      (node (ref "J8") (pin "2@4") (pinfunction "GND_2@4") (pintype "power_in"))
      (node (ref "J8") (pin "2@5") (pinfunction "GND_2@5") (pintype "power_in"))
      (node (ref "J8") (pin "2@6") (pinfunction "GND_2@6") (pintype "power_in"))
      (node (ref "R10") (pin "2") (pinfunction "2_2") (pintype "passive"))
      (node (ref "R4") (pin "1") (pinfunction "1_1") (pintype "passive"))
      (node (ref "RA00") (pin "1") (pinfunction "1_1") (pintype "passive"))
      (node (ref "RA10") (pin "1") (pinfunction "1_1") (pintype "passive"))
      (node (ref "RA20") (pin "1") (pinfunction "1_1") (pintype "passive"))
      (node (ref "RWP0") (pin "1") (pinfunction "1_1") (pintype "passive"))
      (node (ref "SW1") (pin "3") (pinfunction "3_3") (pintype "passive"))
      (node (ref "SW2") (pin "3") (pinfunction "3_3") (pintype "passive"))
      (node (ref "SW3") (pin "3") (pinfunction "3_3") (pintype "passive"))
      (node (ref "SW4") (pin "3") (pinfunction "3_3") (pintype "passive"))
      (node (ref "X1") (pin "1") (pinfunction "1_1") (pintype "passive"))
      (node (ref "X1") (pin "2") (pinfunction "2_2") (pintype "power_in"))
      (node (ref "X1") (pin "4") (pinfunction "4_4") (pintype "power_in"))
      (node (ref "X2") (pin "2") (pinfunction "GND_2") (pintype "power_in"))
    )
    (net (code "31") (name "DIN") (class "Default")
      (node (ref "J1") (pin "20") (pinfunction "20_20") (pintype "passive"))
      (node (ref "U1") (pin "19") (pinfunction "DIN_19") (pintype "input"))
    )
    (net (code "32") (name "I2C_SCL") (class "Default")
      (node (ref "IC1") (pin "6") (pinfunction "SCL_6") (pintype "input"))
      (node (ref "J1") (pin "26") (pinfunction "26_26") (pintype "passive"))
      (node (ref "R1") (pin "1") (pinfunction "1_1") (pintype "passive"))
    )
    (net (code "33") (name "I2C_SDA") (class "Default")
      (node (ref "IC1") (pin "5") (pinfunction "SDA_5") (pintype "bidirectional"))
      (node (ref "J1") (pin "28") (pinfunction "28_28") (pintype "passive"))
      (node (ref "R2") (pin "1") (pinfunction "1_1") (pintype "passive"))
    )
    (net (code "34") (name "LD") (class "Default")
      (node (ref "J1") (pin "13") (pinfunction "13_13") (pintype "passive"))
      (node (ref "U1") (pin "22") (pinfunction "LD_22") (pintype "output"))
    )
    (net (code "35") (name "Net-(C64-Pad1)") (class "Default")
      (node (ref "C64") (pin "1") (pinfunction "1_1") (pintype "passive"))
      (node (ref "R65") (pin "2") (pinfunction "2_2") (pintype "passive"))
      (node (ref "R66") (pin "1") (pinfunction "1_1") (pintype "passive"))
    )
    (net (code "36") (name "Net-(C74-Pad1)") (class "Default")
      (node (ref "C74") (pin "1") (pinfunction "1_1") (pintype "passive"))
      (node (ref "R75") (pin "2") (pinfunction "2_2") (pintype "passive"))
      (node (ref "R76") (pin "1") (pinfunction "1_1") (pintype "passive"))
    )
    (net (code "37") (name "Net-(C119-Pad1)") (class "Default")
      (node (ref "C119") (pin "1") (pinfunction "1_1") (pintype "passive"))
      (node (ref "R102") (pin "2") (pinfunction "2_2") (pintype "passive"))
    )
    (net (code "38") (name "Net-(C128-Pad1)") (class "Default")
      (node (ref "C128") (pin "1") (pinfunction "1_1") (pintype "passive"))
      (node (ref "X1") (pin "3") (pinfunction "3_3") (pintype "passive"))
    )
    (net (code "39") (name "Net-(J2-Pad1)") (class "Default")
      (node (ref "J2") (pin "1") (pinfunction "1_1") (pintype "passive"))
      (node (ref "U2") (pin "1") (pinfunction "1_1") (pintype "bidirectional"))
    )
    (net (code "40") (name "Net-(J3-Pad1)") (class "Default")
      (node (ref "J3") (pin "1") (pinfunction "1_1") (pintype "passive"))
      (node (ref "U3") (pin "1") (pinfunction "1_1") (pintype "bidirectional"))
    )
    (net (code "41") (name "Net-(J4-Pad1)") (class "Default")
      (node (ref "J4") (pin "1") (pinfunction "1_1") (pintype "passive"))
      (node (ref "R41") (pin "2") (pinfunction "2_2") (pintype "passive"))
      (node (ref "R43") (pin "1") (pinfunction "1_1") (pintype "passive"))
    )
    (net (code "42") (name "Net-(J5-Pad1)") (class "Default")
      (node (ref "J5") (pin "1") (pinfunction "1_1") (pintype "passive"))
      (node (ref "R51") (pin "2") (pinfunction "2_2") (pintype "passive"))
      (node (ref "R53") (pin "1") (pinfunction "1_1") (pintype "passive"))
    )
    (net (code "43") (name "Net-(J6-Pad1)") (class "Default")
      (node (ref "J6") (pin "1") (pinfunction "1_1") (pintype "passive"))
      (node (ref "R66") (pin "2") (pinfunction "2_2") (pintype "passive"))
    )
    (net (code "44") (name "Net-(J7-Pad1)") (class "Default")
      (node (ref "J7") (pin "1") (pinfunction "1_1") (pintype "passive"))
      (node (ref "R76") (pin "2") (pinfunction "2_2") (pintype "passive"))
    )
    (net (code "45") (name "Net-(R42-Pad2)") (class "Default")
      (node (ref "R42") (pin "2") (pinfunction "2_2") (pintype "passive"))
      (node (ref "R44") (pin "1") (pinfunction "1_1") (pintype "passive"))
    )
    (net (code "46") (name "Net-(R52-Pad2)") (class "Default")
      (node (ref "R52") (pin "2") (pinfunction "2_2") (pintype "passive"))
      (node (ref "R54") (pin "1") (pinfunction "1_1") (pintype "passive"))
    )
    (net (code "47") (name "Net-(U1A-ANT1+)") (class "Default")
      (node (ref "U1") (pin "4") (pinfunction "ANT1+_4") (pintype "bidirectional"))
      (node (ref "U2") (pin "4") (pinfunction "4_4") (pintype "bidirectional"))
    )
    (net (code "48") (name "Net-(U1A-ANT1-)") (class "Default")
      (node (ref "U1") (pin "5") (pinfunction "ANT1-_5") (pintype "bidirectional"))
      (node (ref "U2") (pin "3") (pinfunction "3_3") (pintype "bidirectional"))
    )
    (net (code "49") (name "Net-(U1A-ANT2+)") (class "Default")
      (node (ref "U1") (pin "9") (pinfunction "ANT2+_9") (pintype "bidirectional"))
      (node (ref "U3") (pin "4") (pinfunction "4_4") (pintype "bidirectional"))
    )
    (net (code "50") (name "Net-(U1A-ANT2-)") (class "Default")
      (node (ref "U1") (pin "10") (pinfunction "ANT2-_10") (pintype "bidirectional"))
      (node (ref "U3") (pin "3") (pinfunction "3_3") (pintype "bidirectional"))
    )
    (net (code "51") (name "Net-(U1D-CLOCKOUT)") (class "Default")
      (node (ref "R5") (pin "2") (pinfunction "2_2") (pintype "passive"))
      (node (ref "U1") (pin "21") (pinfunction "CLOCKOUT_21") (pintype "output"))
    )
    (net (code "52") (name "Net-(U1D-CPOUT)") (class "Default")
      (node (ref "C120") (pin "1") (pinfunction "1_1") (pintype "passive"))
      (node (ref "R101") (pin "1") (pinfunction "1_1") (pintype "passive"))
      (node (ref "R102") (pin "1") (pinfunction "1_1") (pintype "passive"))
      (node (ref "U1") (pin "24") (pinfunction "CPOUT_24") (pintype "output"))
    )
    (net (code "53") (name "Net-(U1D-CTUNE)") (class "Default")
      (node (ref "C126") (pin "2") (pinfunction "2_2") (pintype "passive"))
      (node (ref "C127") (pin "1") (pinfunction "1_1") (pintype "passive"))
      (node (ref "U1") (pin "29") (pinfunction "CTUNE_29") (pintype "input"))
    )
    (net (code "54") (name "Net-(U1D-TUNE)") (class "Default")
      (node (ref "C118") (pin "1") (pinfunction "1_1") (pintype "passive"))
      (node (ref "R101") (pin "2") (pinfunction "2_2") (pintype "passive"))
      (node (ref "U1") (pin "32") (pinfunction "TUNE_32") (pintype "input"))
    )
    (net (code "55") (name "Net-(U1D-XTAL)") (class "Default")
      (node (ref "C121") (pin "1") (pinfunction "1_1") (pintype "passive"))
      (node (ref "C127") (pin "2") (pinfunction "2_2") (pintype "passive"))
      (node (ref "C128") (pin "2") (pinfunction "2_2") (pintype "passive"))
      (node (ref "U1") (pin "28") (pinfunction "XTAL_28") (pintype "input"))
    )
    (net (code "56") (name "Net-(U4-+IN)") (class "Default")
      (node (ref "R43") (pin "2") (pinfunction "2_2") (pintype "passive"))
      (node (ref "R45") (pin "1") (pinfunction "1_1") (pintype "passive"))
      (node (ref "U4") (pin "8") (pinfunction "+IN_8") (pintype "input"))
    )
    (net (code "57") (name "Net-(U4-+OUT)") (class "Default")
      (node (ref "R46") (pin "2") (pinfunction "2_2") (pintype "passive"))
      (node (ref "R48") (pin "1") (pinfunction "1_1") (pintype "passive"))
      (node (ref "U4") (pin "4") (pinfunction "+OUT_4") (pintype "output"))
    )
    (net (code "58") (name "Net-(U4--IN)") (class "Default")
      (node (ref "R44") (pin "2") (pinfunction "2_2") (pintype "passive"))
      (node (ref "R46") (pin "1") (pinfunction "1_1") (pintype "passive"))
      (node (ref "U4") (pin "1") (pinfunction "-IN_1") (pintype "input"))
    )
    (net (code "59") (name "Net-(U4--OUT)") (class "Default")
      (node (ref "R45") (pin "2") (pinfunction "2_2") (pintype "passive"))
      (node (ref "R47") (pin "1") (pinfunction "1_1") (pintype "passive"))
      (node (ref "U4") (pin "5") (pinfunction "-OUT_5") (pintype "output"))
    )
    (net (code "60") (name "Net-(U5-+IN)") (class "Default")
      (node (ref "R53") (pin "2") (pinfunction "2_2") (pintype "passive"))
      (node (ref "R55") (pin "1") (pinfunction "1_1") (pintype "passive"))
      (node (ref "U5") (pin "8") (pinfunction "+IN_8") (pintype "input"))
    )
    (net (code "61") (name "Net-(U5-+OUT)") (class "Default")
      (node (ref "R56") (pin "2") (pinfunction "2_2") (pintype "passive"))
      (node (ref "R58") (pin "1") (pinfunction "1_1") (pintype "passive"))
      (node (ref "U5") (pin "4") (pinfunction "+OUT_4") (pintype "output"))
    )
    (net (code "62") (name "Net-(U5--IN)") (class "Default")
      (node (ref "R54") (pin "2") (pinfunction "2_2") (pintype "passive"))
      (node (ref "R56") (pin "1") (pinfunction "1_1") (pintype "passive"))
      (node (ref "U5") (pin "1") (pinfunction "-IN_1") (pintype "input"))
    )
    (net (code "63") (name "Net-(U5--OUT)") (class "Default")
      (node (ref "R55") (pin "2") (pinfunction "2_2") (pintype "passive"))
      (node (ref "R57") (pin "1") (pinfunction "1_1") (pintype "passive"))
      (node (ref "U5") (pin "5") (pinfunction "-OUT_5") (pintype "output"))
    )
    (net (code "64") (name "Net-(U6-+IN)") (class "Default")
      (node (ref "R61") (pin "2") (pinfunction "2_2") (pintype "passive"))
      (node (ref "R63") (pin "1") (pinfunction "1_1") (pintype "passive"))
      (node (ref "U6") (pin "8") (pinfunction "+IN_8") (pintype "input"))
    )
    (net (code "65") (name "Net-(U6-+OUT)") (class "Default")
      (node (ref "R64") (pin "2") (pinfunction "2_2") (pintype "passive"))
      (node (ref "U6") (pin "4") (pinfunction "+OUT_4") (pintype "output"))
    )
    (net (code "66") (name "Net-(U6--IN)") (class "Default")
      (node (ref "R62") (pin "2") (pinfunction "2_2") (pintype "passive"))
      (node (ref "R64") (pin "1") (pinfunction "1_1") (pintype "passive"))
      (node (ref "U6") (pin "1") (pinfunction "-IN_1") (pintype "input"))
    )
    (net (code "67") (name "Net-(U6--OUT)") (class "Default")
      (node (ref "R63") (pin "2") (pinfunction "2_2") (pintype "passive"))
      (node (ref "R65") (pin "1") (pinfunction "1_1") (pintype "passive"))
      (node (ref "U6") (pin "5") (pinfunction "-OUT_5") (pintype "output"))
    )
    (net (code "68") (name "Net-(U7-+IN)") (class "Default")
      (node (ref "R71") (pin "2") (pinfunction "2_2") (pintype "passive"))
      (node (ref "R73") (pin "1") (pinfunction "1_1") (pintype "passive"))
      (node (ref "U7") (pin "8") (pinfunction "+IN_8") (pintype "input"))
    )
    (net (code "69") (name "Net-(U7-+OUT)") (class "Default")
      (node (ref "R74") (pin "2") (pinfunction "2_2") (pintype "passive"))
      (node (ref "U7") (pin "4") (pinfunction "+OUT_4") (pintype "output"))
    )
    (net (code "70") (name "Net-(U7--IN)") (class "Default")
      (node (ref "R72") (pin "2") (pinfunction "2_2") (pintype "passive"))
      (node (ref "R74") (pin "1") (pinfunction "1_1") (pintype "passive"))
      (node (ref "U7") (pin "1") (pinfunction "-IN_1") (pintype "input"))
    )
    (net (code "71") (name "Net-(U7--OUT)") (class "Default")
      (node (ref "R73") (pin "2") (pinfunction "2_2") (pintype "passive"))
      (node (ref "R75") (pin "1") (pinfunction "1_1") (pintype "passive"))
      (node (ref "U7") (pin "5") (pinfunction "-OUT_5") (pintype "output"))
    )
    (net (code "72") (name "Net-(X2-FO)") (class "Default")
      (node (ref "C121") (pin "2") (pinfunction "2_2") (pintype "passive"))
      (node (ref "R6") (pin "2") (pinfunction "2_2") (pintype "passive"))
      (node (ref "X2") (pin "3") (pinfunction "FO_3") (pintype "output"))
    )
    (net (code "73") (name "Net-(X2-VCC)") (class "Default")
      (node (ref "C123") (pin "1") (pinfunction "1_1") (pintype "passive"))
      (node (ref "C124") (pin "1") (pinfunction "1_1") (pintype "passive"))
      (node (ref "C125") (pin "1") (pinfunction "1_1") (pintype "passive"))
      (node (ref "R7") (pin "1") (pinfunction "1_1") (pintype "passive"))
      (node (ref "X2") (pin "4") (pinfunction "VCC_4") (pintype "power_in"))
    )
    (net (code "74") (name "RSSI") (class "Default")
      (node (ref "J1") (pin "39") (pinfunction "39_39") (pintype "passive"))
      (node (ref "U1") (pin "16") (pinfunction "RSSI_16") (pintype "output"))
    )
    (net (code "75") (name "RXBBI+") (class "Default")
      (node (ref "J1") (pin "52") (pinfunction "52_52") (pintype "passive"))
      (node (ref "U1") (pin "38") (pinfunction "RXBBI+_38") (pintype "output"))
    )
    (net (code "76") (name "RXBBI-") (class "Default")
      (node (ref "J1") (pin "50") (pinfunction "50_50") (pintype "passive"))
      (node (ref "U1") (pin "37") (pinfunction "RXBBI-_37") (pintype "output"))
    )
    (net (code "77") (name "RXBBQ+") (class "Default")
      (node (ref "J1") (pin "46") (pinfunction "46_46") (pintype "passive"))
      (node (ref "U1") (pin "36") (pinfunction "RXBBQ+_36") (pintype "output"))
    )
    (net (code "78") (name "RXBBQ-") (class "Default")
      (node (ref "J1") (pin "44") (pinfunction "44_44") (pintype "passive"))
      (node (ref "U1") (pin "35") (pinfunction "RXBBQ-_35") (pintype "output"))
    )
    (net (code "79") (name "RXHP") (class "Default")
      (node (ref "SW1") (pin "2") (pinfunction "2_2") (pintype "passive"))
      (node (ref "U1") (pin "40") (pinfunction "RXHP_40") (pintype "input"))
    )
    (net (code "80") (name "RXTX") (class "Default")
      (node (ref "J1") (pin "23") (pinfunction "23_23") (pintype "passive"))
      (node (ref "U1") (pin "48") (pinfunction "RXTX_48") (pintype "input"))
    )
    (net (code "81") (name "SCLK") (class "Default")
      (node (ref "J1") (pin "18") (pinfunction "18_18") (pintype "passive"))
      (node (ref "U1") (pin "18") (pinfunction "SCLK_18") (pintype "input"))
    )
    (net (code "82") (name "TXBBI+") (class "Default")
      (node (ref "J1") (pin "40") (pinfunction "40_40") (pintype "passive"))
      (node (ref "U1") (pin "45") (pinfunction "TXBBI+_45") (pintype "input"))
    )
    (net (code "83") (name "TXBBI-") (class "Default")
      (node (ref "J1") (pin "38") (pinfunction "38_38") (pintype "passive"))
      (node (ref "U1") (pin "44") (pinfunction "TXBBI-_44") (pintype "input"))
    )
    (net (code "84") (name "TXBBQ+") (class "Default")
      (node (ref "J1") (pin "34") (pinfunction "34_34") (pintype "passive"))
      (node (ref "U1") (pin "43") (pinfunction "TXBBQ+_43") (pintype "input"))
    )
    (net (code "85") (name "TXBBQ-") (class "Default")
      (node (ref "J1") (pin "32") (pinfunction "32_32") (pintype "passive"))
      (node (ref "U1") (pin "42") (pinfunction "TXBBQ-_42") (pintype "input"))
    )
    (net (code "86") (name "VSUP") (class "Default")
      (node (ref "J1") (pin "3") (pinfunction "3_3") (pintype "passive"))
      (node (ref "J1") (pin "4") (pinfunction "4_4") (pintype "passive"))
    )
    (net (code "87") (name "V_BIAS_ADC") (class "Default")
      (node (ref "C45") (pin "1") (pinfunction "1_1") (pintype "passive"))
      (node (ref "R451") (pin "1") (pinfunction "1_1") (pintype "passive"))
      (node (ref "R452") (pin "2") (pinfunction "2_2") (pintype "passive"))
      (node (ref "U4") (pin "2") (pinfunction "V_OCM_2") (pintype "input"))
      (node (ref "U5") (pin "2") (pinfunction "V_OCM_2") (pintype "input"))
    )
    (net (code "88") (name "V_BIAS_DAC") (class "Default")
      (node (ref "C67") (pin "1") (pinfunction "1_1") (pintype "passive"))
      (node (ref "R671") (pin "1") (pinfunction "1_1") (pintype "passive"))
      (node (ref "R672") (pin "2") (pinfunction "2_2") (pintype "passive"))
      (node (ref "U6") (pin "2") (pinfunction "V_OCM_2") (pintype "input"))
      (node (ref "U7") (pin "2") (pinfunction "V_OCM_2") (pintype "input"))
    )
    (net (code "89") (name "WP") (class "Default")
      (node (ref "IC1") (pin "7") (pinfunction "WP_7") (pintype "input"))
      (node (ref "RWP0") (pin "2") (pinfunction "2_2") (pintype "passive"))
      (node (ref "RWP1") (pin "2") (pinfunction "2_2") (pintype "passive"))
    )
    (net (code "90") (name "unconnected-(J1-Pad22)") (class "Default")
      (node (ref "J1") (pin "22") (pinfunction "22_22") (pintype "passive"))
    )
    (net (code "91") (name "unconnected-(J1-Pad25)") (class "Default")
      (node (ref "J1") (pin "25") (pinfunction "25_25") (pintype "passive"))
    )
    (net (code "92") (name "unconnected-(J1-Pad27)") (class "Default")
      (node (ref "J1") (pin "27") (pinfunction "27_27") (pintype "passive"))
    )
    (net (code "93") (name "unconnected-(J1-Pad31)") (class "Default")
      (node (ref "J1") (pin "31") (pinfunction "31_31") (pintype "passive"))
    )
    (net (code "94") (name "unconnected-(J1-Pad33)") (class "Default")
      (node (ref "J1") (pin "33") (pinfunction "33_33") (pintype "passive"))
    )
    (net (code "95") (name "unconnected-(J1-Pad37)") (class "Default")
      (node (ref "J1") (pin "37") (pinfunction "37_37") (pintype "passive"))
    )
    (net (code "96") (name "unconnected-(J1-Pad43)") (class "Default")
      (node (ref "J1") (pin "43") (pinfunction "43_43") (pintype "passive"))
    )
    (net (code "97") (name "unconnected-(J1-Pad45)") (class "Default")
      (node (ref "J1") (pin "45") (pinfunction "45_45") (pintype "passive"))
    )
    (net (code "98") (name "unconnected-(J1-Pad49)") (class "Default")
      (node (ref "J1") (pin "49") (pinfunction "49_49") (pintype "passive"))
    )
    (net (code "99") (name "unconnected-(J1-Pad51)") (class "Default")
      (node (ref "J1") (pin "51") (pinfunction "51_51") (pintype "passive"))
    )
    (net (code "100") (name "unconnected-(J1-Pad55)") (class "Default")
      (node (ref "J1") (pin "55") (pinfunction "55_55") (pintype "passive"))
    )
    (net (code "101") (name "unconnected-(J1-Pad57)") (class "Default")
      (node (ref "J1") (pin "57") (pinfunction "57_57") (pintype "passive"))
    )
    (net (code "102") (name "unconnected-(J1-Pad61)") (class "Default")
      (node (ref "J1") (pin "61") (pinfunction "61_61") (pintype "passive"))
    )
    (net (code "103") (name "unconnected-(J1-Pad63)") (class "Default")
      (node (ref "J1") (pin "63") (pinfunction "63_63") (pintype "passive"))
    )
    (net (code "104") (name "unconnected-(J1-Pad67)") (class "Default")
      (node (ref "J1") (pin "67") (pinfunction "67_67") (pintype "passive"))
    )
    (net (code "105") (name "unconnected-(J1-Pad69)") (class "Default")
      (node (ref "J1") (pin "69") (pinfunction "69_69") (pintype "passive"))
    )
    (net (code "106") (name "unconnected-(J1-Pad73)") (class "Default")
      (node (ref "J1") (pin "73") (pinfunction "73_73") (pintype "passive"))
    )
    (net (code "107") (name "unconnected-(J1-Pad75)") (class "Default")
      (node (ref "J1") (pin "75") (pinfunction "75_75") (pintype "passive"))
    )
    (net (code "108") (name "unconnected-(U2-Pad6)") (class "Default")
      (node (ref "U2") (pin "6") (pinfunction "6_6") (pintype "no_connect"))
    )
    (net (code "109") (name "unconnected-(U3-Pad6)") (class "Default")
      (node (ref "U3") (pin "6") (pinfunction "6_6") (pintype "no_connect"))
    )
    (net (code "110") (name "unconnected-(U4-PD-Pad7)") (class "Default")
      (node (ref "U4") (pin "7") (pinfunction "PD_7") (pintype "input"))
    )
    (net (code "111") (name "unconnected-(U5-PD-Pad7)") (class "Default")
      (node (ref "U5") (pin "7") (pinfunction "PD_7") (pintype "input"))
    )
    (net (code "112") (name "unconnected-(U6-PD-Pad7)") (class "Default")
      (node (ref "U6") (pin "7") (pinfunction "PD_7") (pintype "input"))
    )
    (net (code "113") (name "unconnected-(U7-PD-Pad7)") (class "Default")
      (node (ref "U7") (pin "7") (pinfunction "PD_7") (pintype "input"))
    )
    (net (code "114") (name "unconnected-(X2-NC-Pad1)") (class "Default")
      (node (ref "X2") (pin "1") (pinfunction "NC_1") (pintype "no_connect"))
    )
    (net (code "115") (name "~{CS}") (class "Default")
      (node (ref "J1") (pin "24") (pinfunction "24_24") (pintype "passive"))
      (node (ref "U1") (pin "15") (pinfunction "/CS_15") (pintype "input"))
    )
    (net (code "116") (name "~{SHDN}") (class "Default")
      (node (ref "J1") (pin "17") (pinfunction "17_17") (pintype "passive"))
      (node (ref "R10") (pin "1") (pinfunction "1_1") (pintype "passive"))
      (node (ref "U1") (pin "12") (pinfunction "/SHDN_12") (pintype "input"))
    )
  )
)
